# SOM_MCU.net
KiCad netlist of a schematic drawn in Altium Designer
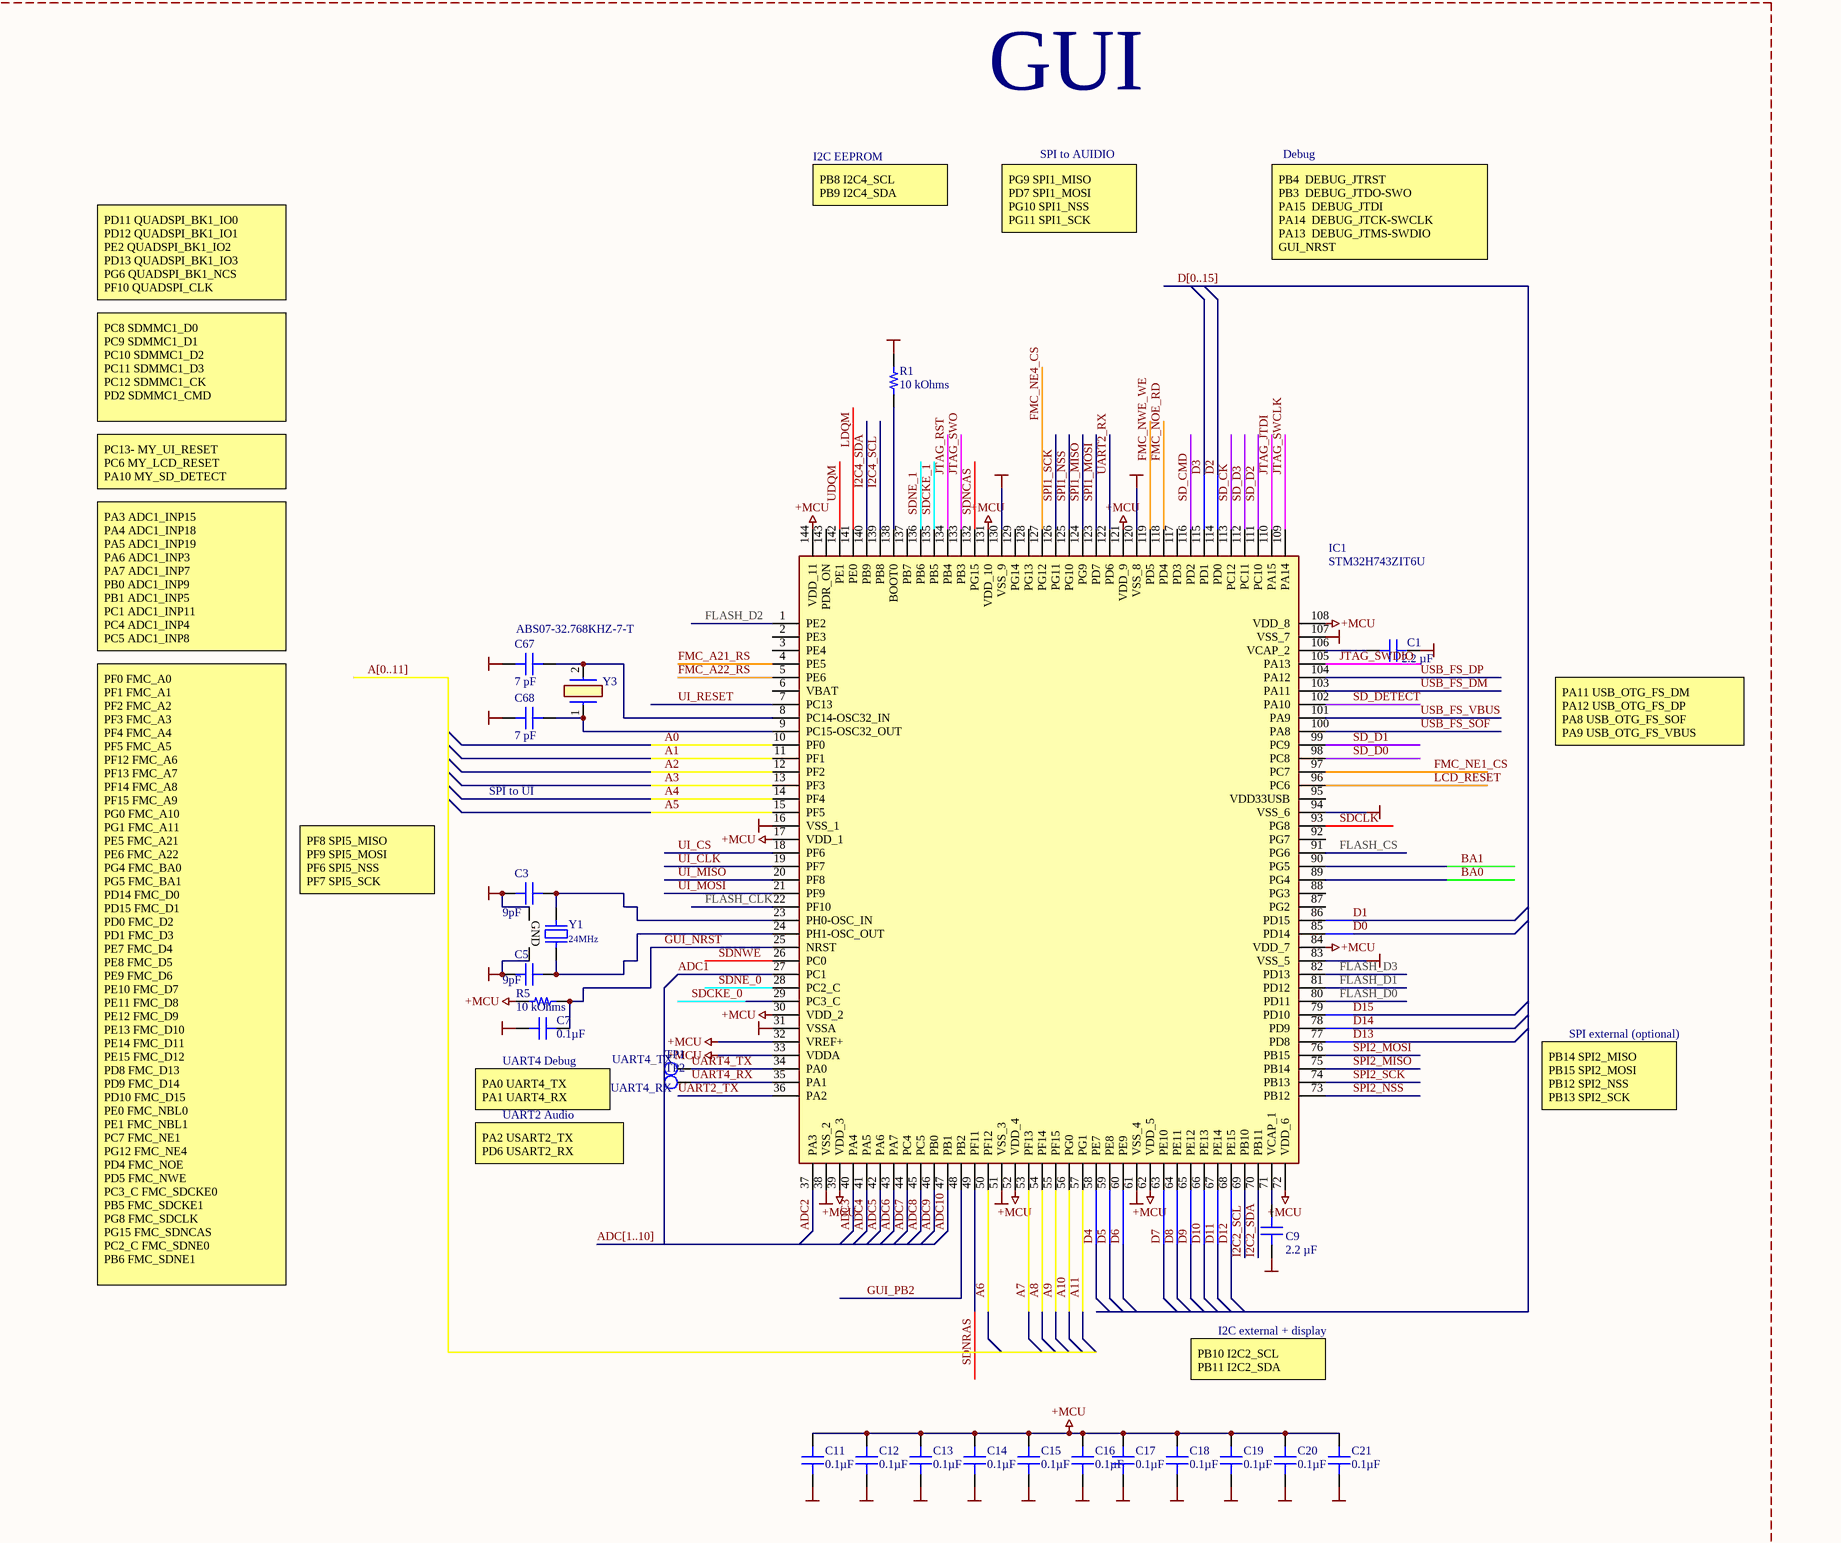
[diagram p0: SOM_MCU.SchDoc, top left]
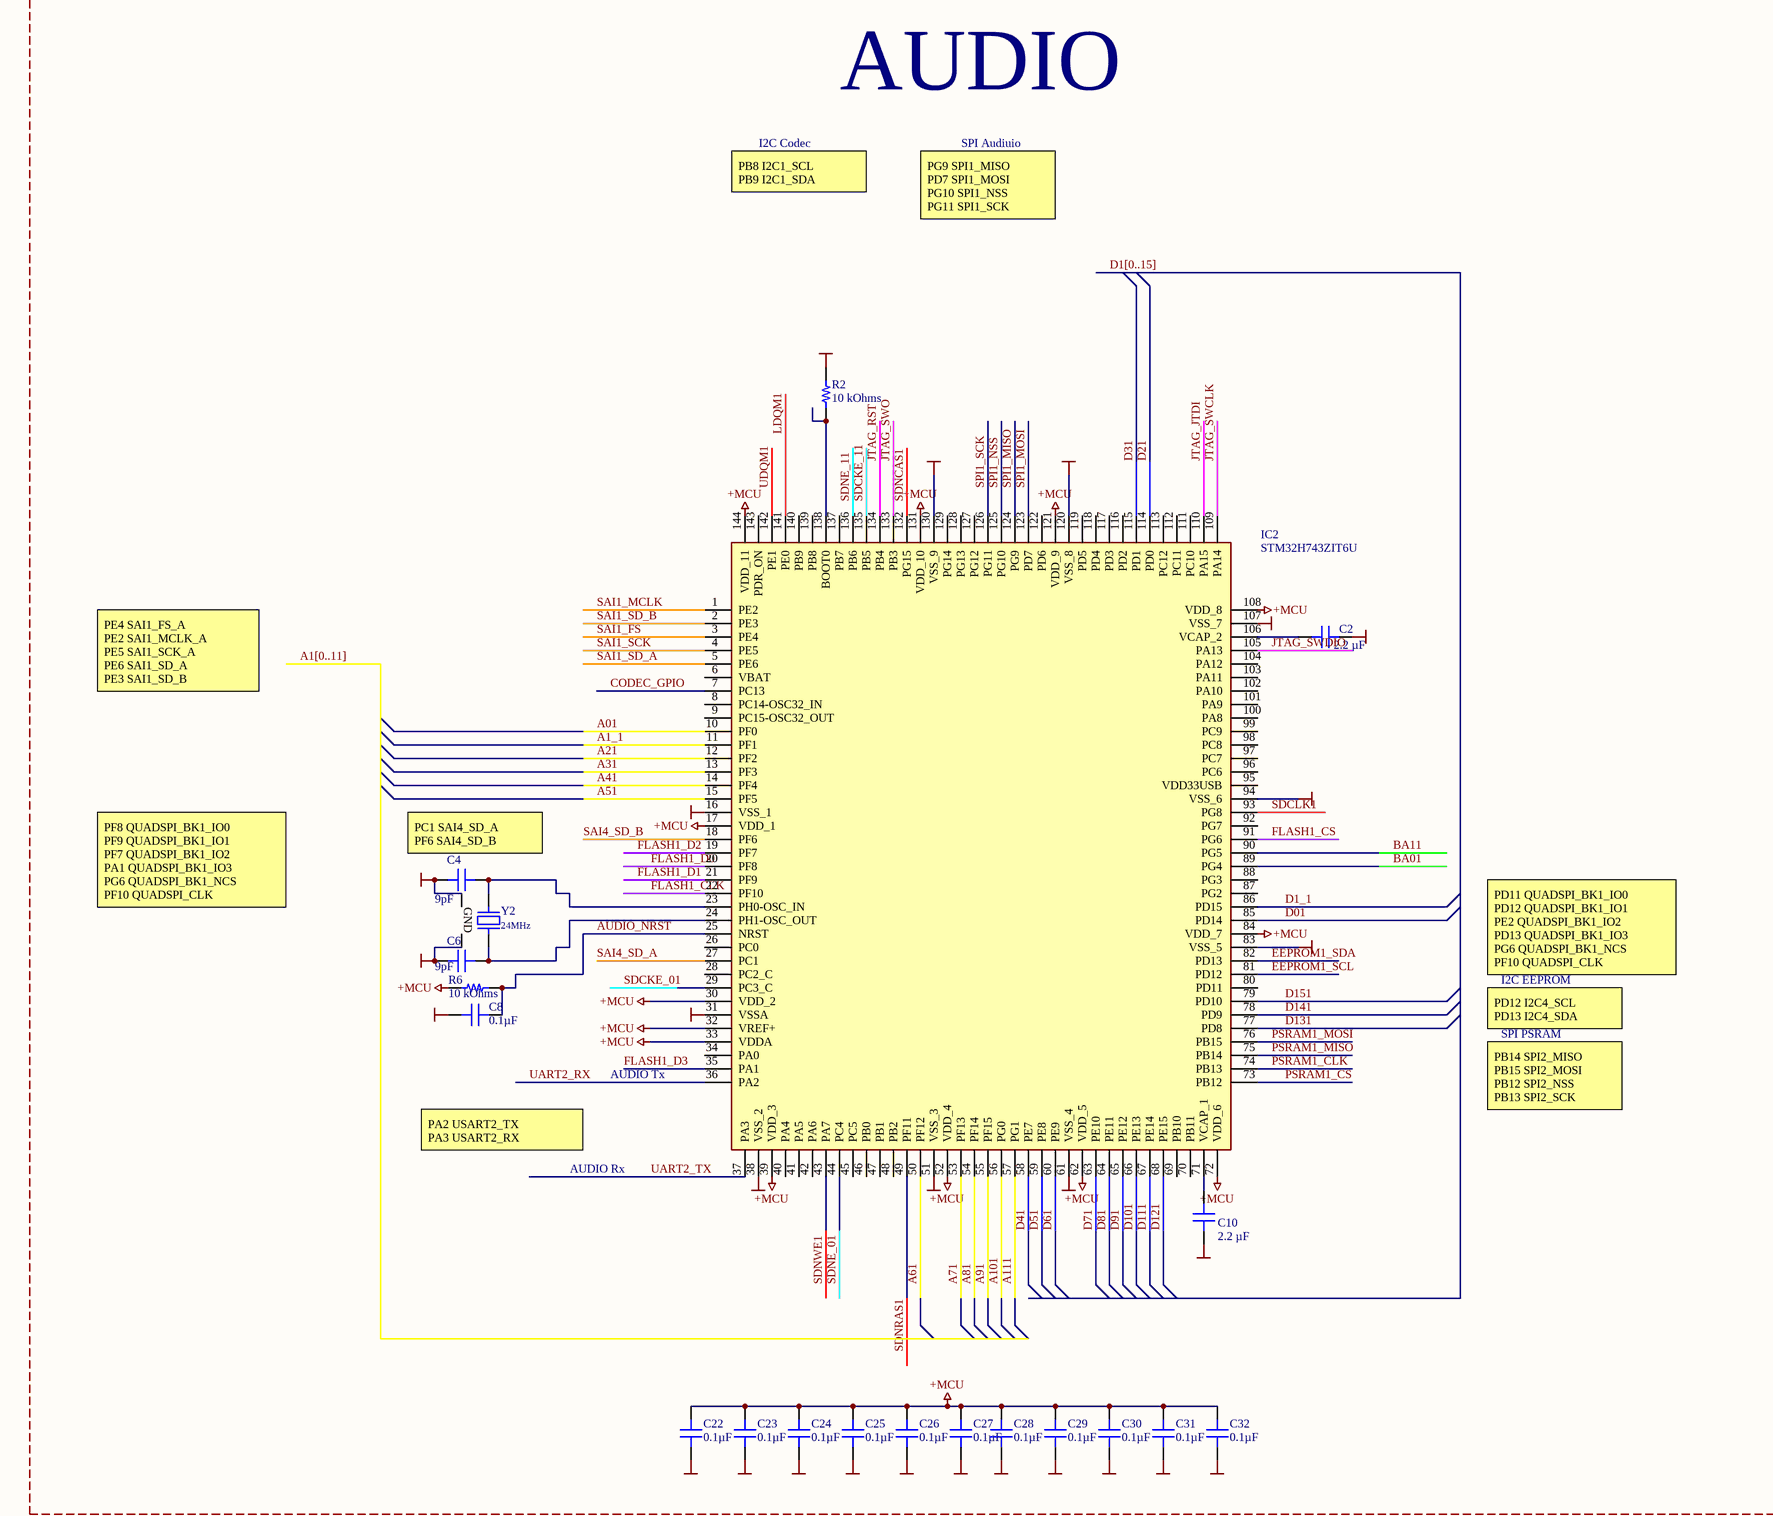
[diagram p1: SOM_MCU.SchDoc, top right]
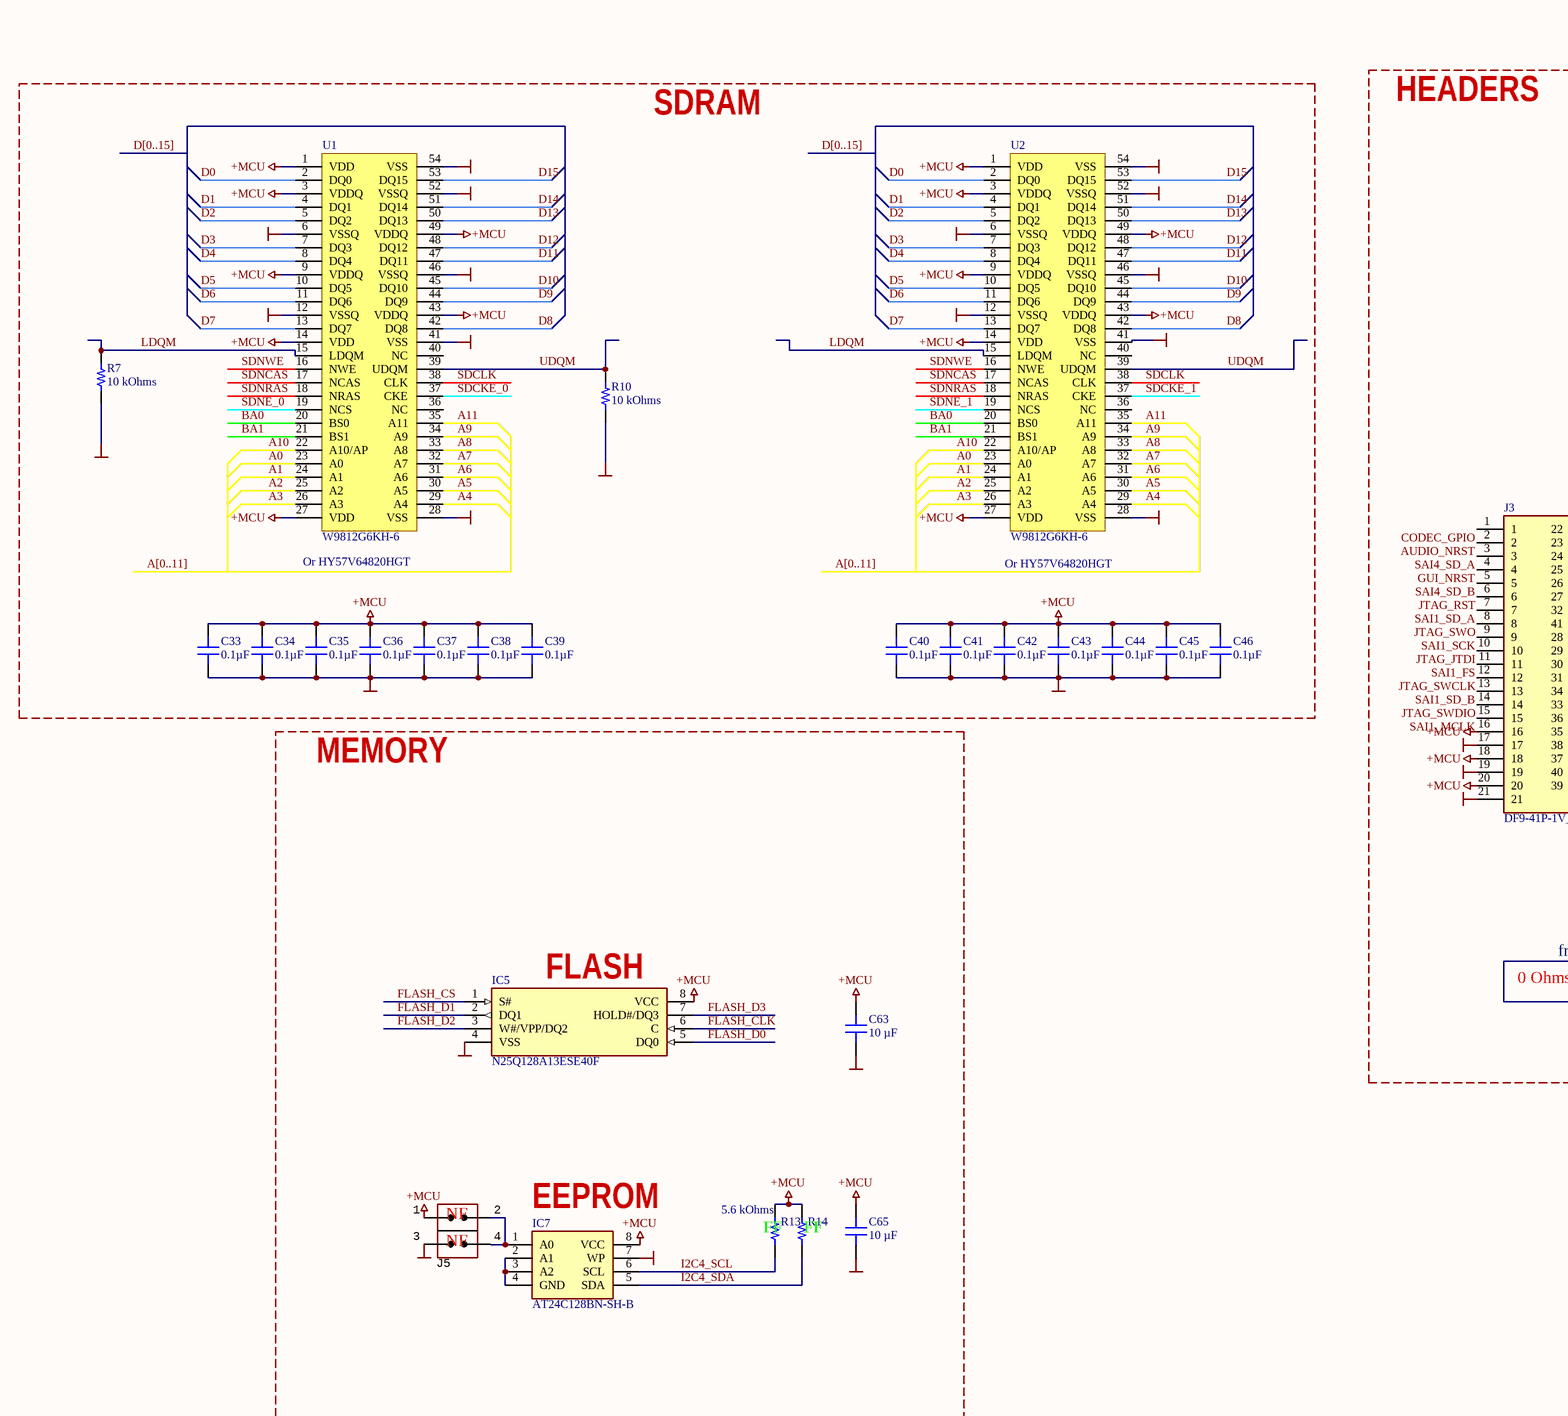
[diagram p2: SOM_MCU.SchDoc, bottom left]
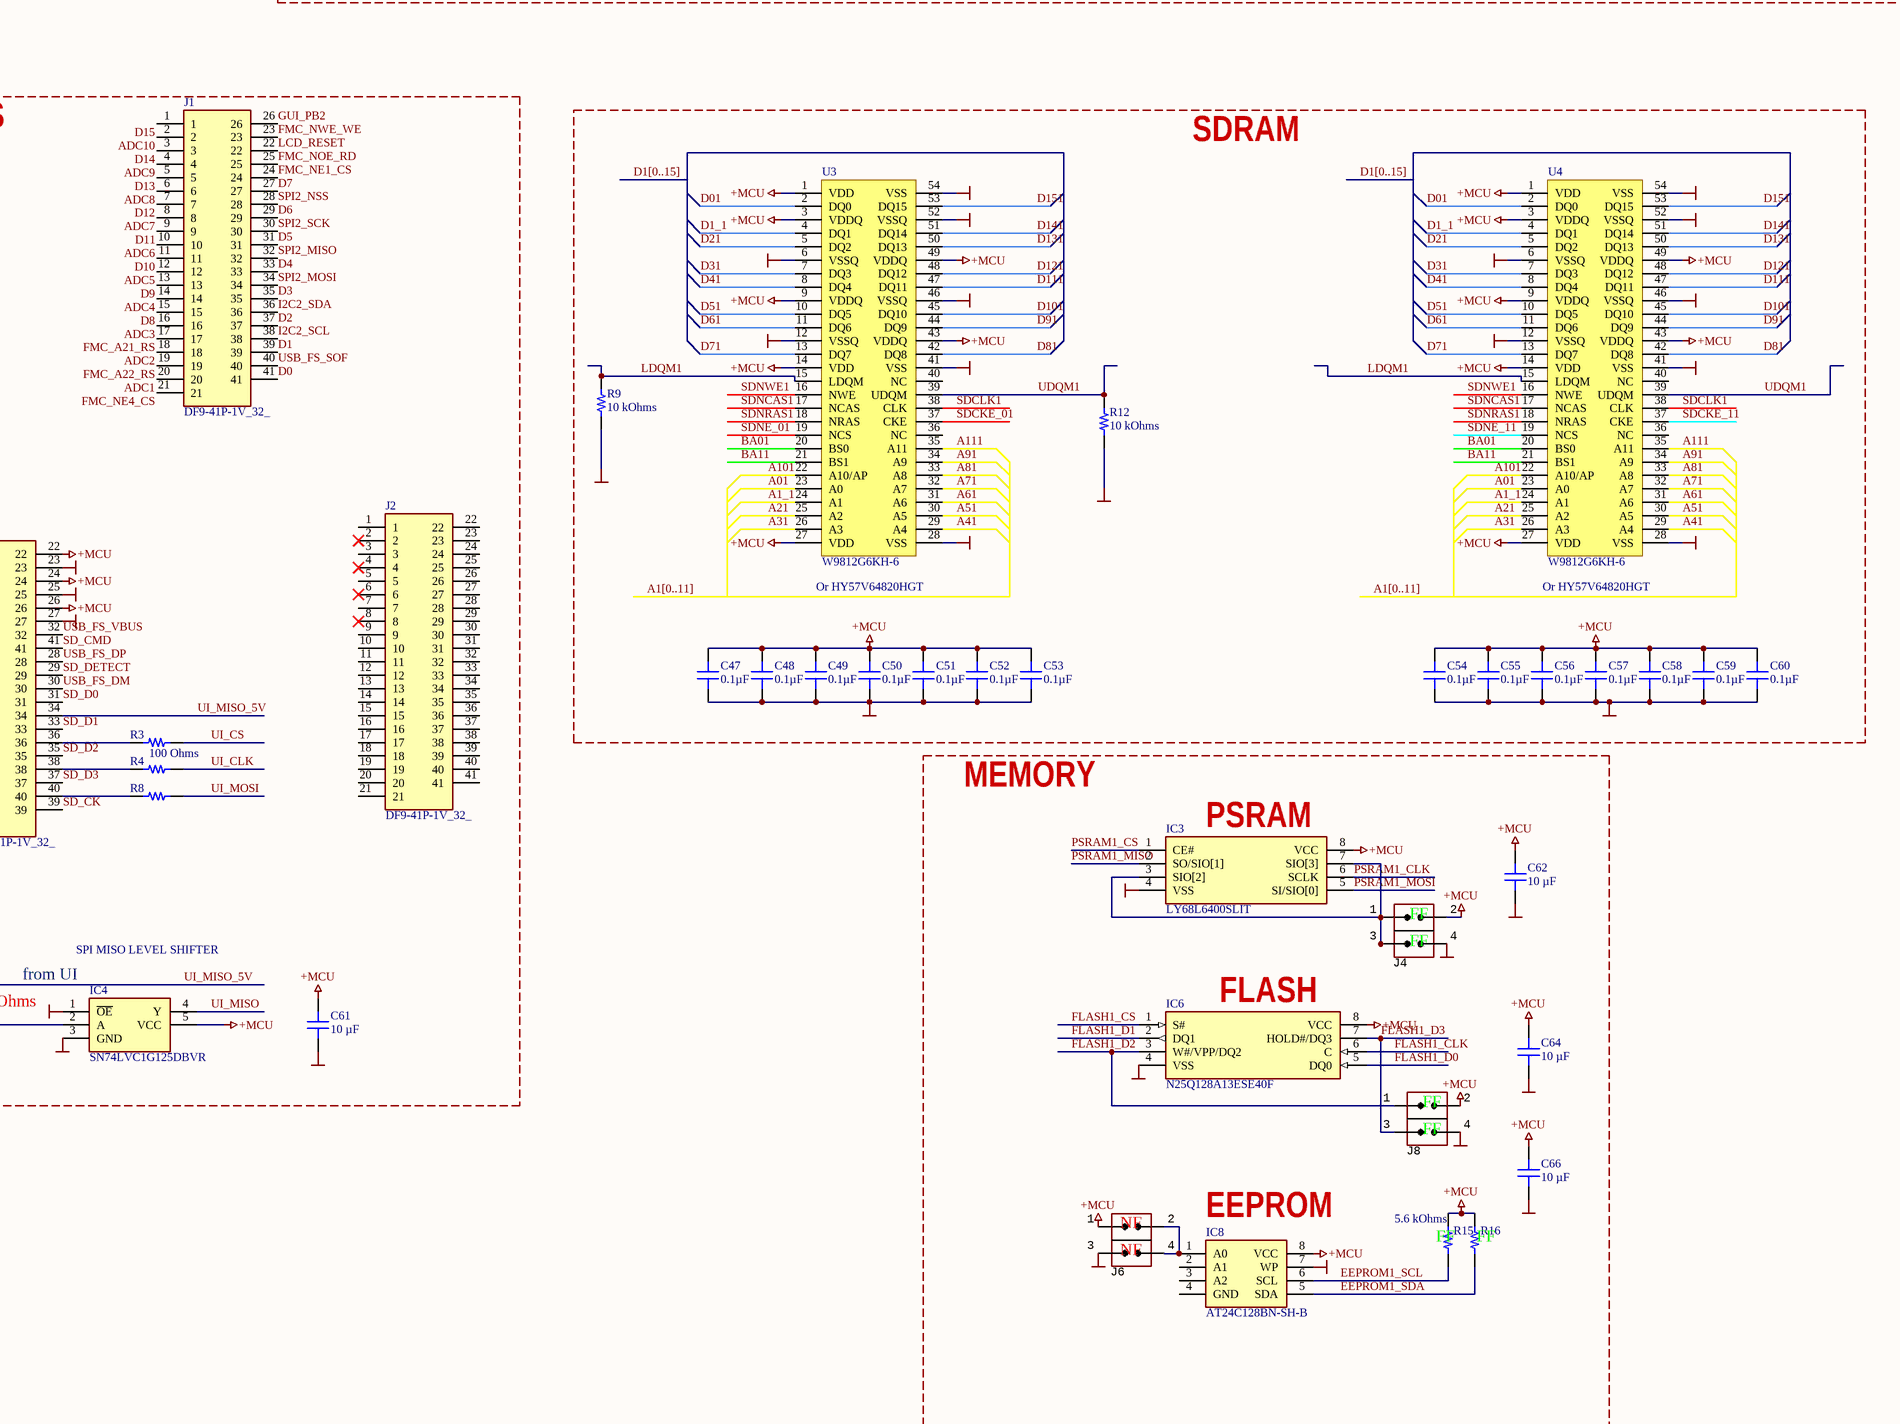
[diagram p3: SOM_MCU.SchDoc, bottom right]

(export (version "E")
  (design (tool "Eeschema 10.0.6"))
  (components
    (comp (ref "C1")
      (value "2.2 µF")
      (footprint "CAP 0805_2012")
      (description "CAP CER 2.2UF 10V X7R 0805")
      (fields (field (name "PART NUMBER") "C0805C225K8RAC7800") (field (name "MANUFACTURER") "KEMET"))
      (libsource (lib "Celestial Altium Library - altium_library") (part "Capacitor"))
    )
    (comp (ref "C2")
      (value "2.2 µF")
      (footprint "CAP 0805_2012")
      (description "CAP CER 2.2UF 10V X7R 0805")
      (fields (field (name "PART NUMBER") "C0805C225K8RAC7800") (field (name "MANUFACTURER") "KEMET"))
      (libsource (lib "Celestial Altium Library - altium_library") (part "Capacitor"))
    )
    (comp (ref "C3")
      (value "9pF")
      (footprint "CAP 0805_2012")
      (description "CAP CER 9PF 250V C0G/NP0 0805")
      (fields (field (name "PART NUMBER") "CBR08C909CAGAC") (field (name "MANUFACTURER") "KEMET"))
      (libsource (lib "Celestial Altium Library - altium_library") (part "Capacitor"))
    )
    (comp (ref "C4")
      (value "9pF")
      (footprint "CAP 0805_2012")
      (description "CAP CER 9PF 250V C0G/NP0 0805")
      (fields (field (name "PART NUMBER") "CBR08C909CAGAC") (field (name "MANUFACTURER") "KEMET"))
      (libsource (lib "Celestial Altium Library - altium_library") (part "Capacitor"))
    )
    (comp (ref "C5")
      (value "9pF")
      (footprint "CAP 0805_2012")
      (description "CAP CER 9PF 250V C0G/NP0 0805")
      (fields (field (name "PART NUMBER") "CBR08C909CAGAC") (field (name "MANUFACTURER") "KEMET"))
      (libsource (lib "Celestial Altium Library - altium_library") (part "Capacitor"))
    )
    (comp (ref "C6")
      (value "9pF")
      (footprint "CAP 0805_2012")
      (description "CAP CER 9PF 250V C0G/NP0 0805")
      (fields (field (name "PART NUMBER") "CBR08C909CAGAC") (field (name "MANUFACTURER") "KEMET"))
      (libsource (lib "Celestial Altium Library - altium_library") (part "Capacitor"))
    )
    (comp (ref "C7")
      (value "0.1µF")
      (footprint "CAP 0402_1005")
      (description "CAP CER 0.1UF 16V X7R 0402")
      (fields (field (name "PART NUMBER") "C0402C104K4RACAUTO") (field (name "MANUFACTURER") "KEMET"))
      (libsource (lib "Celestial Altium Library - altium_library") (part "Capacitor"))
    )
    (comp (ref "C8")
      (value "0.1µF")
      (footprint "CAP 0402_1005")
      (description "CAP CER 0.1UF 16V X7R 0402")
      (fields (field (name "PART NUMBER") "C0402C104K4RACAUTO") (field (name "MANUFACTURER") "KEMET"))
      (libsource (lib "Celestial Altium Library - altium_library") (part "Capacitor"))
    )
    (comp (ref "C9")
      (value "2.2 µF")
      (footprint "CAP 0805_2012")
      (description "CAP CER 2.2UF 10V X7R 0805")
      (fields (field (name "PART NUMBER") "C0805C225K8RAC7800") (field (name "MANUFACTURER") "KEMET"))
      (libsource (lib "Celestial Altium Library - altium_library") (part "Capacitor"))
    )
    (comp (ref "C10")
      (value "2.2 µF")
      (footprint "CAP 0805_2012")
      (description "CAP CER 2.2UF 10V X7R 0805")
      (fields (field (name "PART NUMBER") "C0805C225K8RAC7800") (field (name "MANUFACTURER") "KEMET"))
      (libsource (lib "Celestial Altium Library - altium_library") (part "Capacitor"))
    )
    (comp (ref "C11")
      (value "0.1µF")
      (footprint "CAP 0402_1005")
      (description "CAP CER 0.1UF 16V X7R 0402")
      (fields (field (name "PART NUMBER") "C0402C104K4RACAUTO") (field (name "MANUFACTURER") "KEMET"))
      (libsource (lib "Celestial Altium Library - altium_library") (part "Capacitor"))
    )
    (comp (ref "C12")
      (value "0.1µF")
      (footprint "CAP 0402_1005")
      (description "CAP CER 0.1UF 16V X7R 0402")
      (fields (field (name "PART NUMBER") "C0402C104K4RACAUTO") (field (name "MANUFACTURER") "KEMET"))
      (libsource (lib "Celestial Altium Library - altium_library") (part "Capacitor"))
    )
    (comp (ref "C13")
      (value "0.1µF")
      (footprint "CAP 0402_1005")
      (description "CAP CER 0.1UF 16V X7R 0402")
      (fields (field (name "PART NUMBER") "C0402C104K4RACAUTO") (field (name "MANUFACTURER") "KEMET"))
      (libsource (lib "Celestial Altium Library - altium_library") (part "Capacitor"))
    )
    (comp (ref "C14")
      (value "0.1µF")
      (footprint "CAP 0402_1005")
      (description "CAP CER 0.1UF 16V X7R 0402")
      (fields (field (name "PART NUMBER") "C0402C104K4RACAUTO") (field (name "MANUFACTURER") "KEMET"))
      (libsource (lib "Celestial Altium Library - altium_library") (part "Capacitor"))
    )
    (comp (ref "C15")
      (value "0.1µF")
      (footprint "CAP 0402_1005")
      (description "CAP CER 0.1UF 16V X7R 0402")
      (fields (field (name "PART NUMBER") "C0402C104K4RACAUTO") (field (name "MANUFACTURER") "KEMET"))
      (libsource (lib "Celestial Altium Library - altium_library") (part "Capacitor"))
    )
    (comp (ref "C16")
      (value "0.1µF")
      (footprint "CAP 0402_1005")
      (description "CAP CER 0.1UF 16V X7R 0402")
      (fields (field (name "PART NUMBER") "C0402C104K4RACAUTO") (field (name "MANUFACTURER") "KEMET"))
      (libsource (lib "Celestial Altium Library - altium_library") (part "Capacitor"))
    )
    (comp (ref "C17")
      (value "0.1µF")
      (footprint "CAP 0402_1005")
      (description "CAP CER 0.1UF 16V X7R 0402")
      (fields (field (name "PART NUMBER") "C0402C104K4RACAUTO") (field (name "MANUFACTURER") "KEMET"))
      (libsource (lib "Celestial Altium Library - altium_library") (part "Capacitor"))
    )
    (comp (ref "C18")
      (value "0.1µF")
      (footprint "CAP 0402_1005")
      (description "CAP CER 0.1UF 16V X7R 0402")
      (fields (field (name "PART NUMBER") "C0402C104K4RACAUTO") (field (name "MANUFACTURER") "KEMET"))
      (libsource (lib "Celestial Altium Library - altium_library") (part "Capacitor"))
    )
    (comp (ref "C19")
      (value "0.1µF")
      (footprint "CAP 0402_1005")
      (description "CAP CER 0.1UF 16V X7R 0402")
      (fields (field (name "PART NUMBER") "C0402C104K4RACAUTO") (field (name "MANUFACTURER") "KEMET"))
      (libsource (lib "Celestial Altium Library - altium_library") (part "Capacitor"))
    )
    (comp (ref "C20")
      (value "0.1µF")
      (footprint "CAP 0402_1005")
      (description "CAP CER 0.1UF 16V X7R 0402")
      (fields (field (name "PART NUMBER") "C0402C104K4RACAUTO") (field (name "MANUFACTURER") "KEMET"))
      (libsource (lib "Celestial Altium Library - altium_library") (part "Capacitor"))
    )
    (comp (ref "C21")
      (value "0.1µF")
      (footprint "CAP 0402_1005")
      (description "CAP CER 0.1UF 16V X7R 0402")
      (fields (field (name "PART NUMBER") "C0402C104K4RACAUTO") (field (name "MANUFACTURER") "KEMET"))
      (libsource (lib "Celestial Altium Library - altium_library") (part "Capacitor"))
    )
    (comp (ref "C22")
      (value "0.1µF")
      (footprint "CAP 0402_1005")
      (description "CAP CER 0.1UF 16V X7R 0402")
      (fields (field (name "PART NUMBER") "C0402C104K4RACAUTO") (field (name "MANUFACTURER") "KEMET"))
      (libsource (lib "Celestial Altium Library - altium_library") (part "Capacitor"))
    )
    (comp (ref "C23")
      (value "0.1µF")
      (footprint "CAP 0402_1005")
      (description "CAP CER 0.1UF 16V X7R 0402")
      (fields (field (name "PART NUMBER") "C0402C104K4RACAUTO") (field (name "MANUFACTURER") "KEMET"))
      (libsource (lib "Celestial Altium Library - altium_library") (part "Capacitor"))
    )
    (comp (ref "C24")
      (value "0.1µF")
      (footprint "CAP 0402_1005")
      (description "CAP CER 0.1UF 16V X7R 0402")
      (fields (field (name "PART NUMBER") "C0402C104K4RACAUTO") (field (name "MANUFACTURER") "KEMET"))
      (libsource (lib "Celestial Altium Library - altium_library") (part "Capacitor"))
    )
    (comp (ref "C25")
      (value "0.1µF")
      (footprint "CAP 0402_1005")
      (description "CAP CER 0.1UF 16V X7R 0402")
      (fields (field (name "PART NUMBER") "C0402C104K4RACAUTO") (field (name "MANUFACTURER") "KEMET"))
      (libsource (lib "Celestial Altium Library - altium_library") (part "Capacitor"))
    )
    (comp (ref "C26")
      (value "0.1µF")
      (footprint "CAP 0402_1005")
      (description "CAP CER 0.1UF 16V X7R 0402")
      (fields (field (name "PART NUMBER") "C0402C104K4RACAUTO") (field (name "MANUFACTURER") "KEMET"))
      (libsource (lib "Celestial Altium Library - altium_library") (part "Capacitor"))
    )
    (comp (ref "C27")
      (value "0.1µF")
      (footprint "CAP 0402_1005")
      (description "CAP CER 0.1UF 16V X7R 0402")
      (fields (field (name "PART NUMBER") "C0402C104K4RACAUTO") (field (name "MANUFACTURER") "KEMET"))
      (libsource (lib "Celestial Altium Library - altium_library") (part "Capacitor"))
    )
    (comp (ref "C28")
      (value "0.1µF")
      (footprint "CAP 0402_1005")
      (description "CAP CER 0.1UF 16V X7R 0402")
      (fields (field (name "PART NUMBER") "C0402C104K4RACAUTO") (field (name "MANUFACTURER") "KEMET"))
      (libsource (lib "Celestial Altium Library - altium_library") (part "Capacitor"))
    )
    (comp (ref "C29")
      (value "0.1µF")
      (footprint "CAP 0402_1005")
      (description "CAP CER 0.1UF 16V X7R 0402")
      (fields (field (name "PART NUMBER") "C0402C104K4RACAUTO") (field (name "MANUFACTURER") "KEMET"))
      (libsource (lib "Celestial Altium Library - altium_library") (part "Capacitor"))
    )
    (comp (ref "C30")
      (value "0.1µF")
      (footprint "CAP 0402_1005")
      (description "CAP CER 0.1UF 16V X7R 0402")
      (fields (field (name "PART NUMBER") "C0402C104K4RACAUTO") (field (name "MANUFACTURER") "KEMET"))
      (libsource (lib "Celestial Altium Library - altium_library") (part "Capacitor"))
    )
    (comp (ref "C31")
      (value "0.1µF")
      (footprint "CAP 0402_1005")
      (description "CAP CER 0.1UF 16V X7R 0402")
      (fields (field (name "PART NUMBER") "C0402C104K4RACAUTO") (field (name "MANUFACTURER") "KEMET"))
      (libsource (lib "Celestial Altium Library - altium_library") (part "Capacitor"))
    )
    (comp (ref "C32")
      (value "0.1µF")
      (footprint "CAP 0402_1005")
      (description "CAP CER 0.1UF 16V X7R 0402")
      (fields (field (name "PART NUMBER") "C0402C104K4RACAUTO") (field (name "MANUFACTURER") "KEMET"))
      (libsource (lib "Celestial Altium Library - altium_library") (part "Capacitor"))
    )
    (comp (ref "C33")
      (value "0.1µF")
      (footprint "CAP 0402_1005")
      (description "CAP CER 0.1UF 16V X7R 0402")
      (fields (field (name "PART NUMBER") "C0402C104K4RACAUTO") (field (name "MANUFACTURER") "KEMET"))
      (libsource (lib "Celestial Altium Library - altium_library") (part "Capacitor"))
    )
    (comp (ref "C34")
      (value "0.1µF")
      (footprint "CAP 0402_1005")
      (description "CAP CER 0.1UF 16V X7R 0402")
      (fields (field (name "PART NUMBER") "C0402C104K4RACAUTO") (field (name "MANUFACTURER") "KEMET"))
      (libsource (lib "Celestial Altium Library - altium_library") (part "Capacitor"))
    )
    (comp (ref "C35")
      (value "0.1µF")
      (footprint "CAP 0402_1005")
      (description "CAP CER 0.1UF 16V X7R 0402")
      (fields (field (name "PART NUMBER") "C0402C104K4RACAUTO") (field (name "MANUFACTURER") "KEMET"))
      (libsource (lib "Celestial Altium Library - altium_library") (part "Capacitor"))
    )
    (comp (ref "C36")
      (value "0.1µF")
      (footprint "CAP 0402_1005")
      (description "CAP CER 0.1UF 16V X7R 0402")
      (fields (field (name "PART NUMBER") "C0402C104K4RACAUTO") (field (name "MANUFACTURER") "KEMET"))
      (libsource (lib "Celestial Altium Library - altium_library") (part "Capacitor"))
    )
    (comp (ref "C37")
      (value "0.1µF")
      (footprint "CAP 0402_1005")
      (description "CAP CER 0.1UF 16V X7R 0402")
      (fields (field (name "PART NUMBER") "C0402C104K4RACAUTO") (field (name "MANUFACTURER") "KEMET"))
      (libsource (lib "Celestial Altium Library - altium_library") (part "Capacitor"))
    )
    (comp (ref "C38")
      (value "0.1µF")
      (footprint "CAP 0402_1005")
      (description "CAP CER 0.1UF 16V X7R 0402")
      (fields (field (name "PART NUMBER") "C0402C104K4RACAUTO") (field (name "MANUFACTURER") "KEMET"))
      (libsource (lib "Celestial Altium Library - altium_library") (part "Capacitor"))
    )
    (comp (ref "C39")
      (value "0.1µF")
      (footprint "CAP 0402_1005")
      (description "CAP CER 0.1UF 16V X7R 0402")
      (fields (field (name "PART NUMBER") "C0402C104K4RACAUTO") (field (name "MANUFACTURER") "KEMET"))
      (libsource (lib "Celestial Altium Library - altium_library") (part "Capacitor"))
    )
    (comp (ref "C40")
      (value "0.1µF")
      (footprint "CAP 0402_1005")
      (description "CAP CER 0.1UF 16V X7R 0402")
      (fields (field (name "PART NUMBER") "C0402C104K4RACAUTO") (field (name "MANUFACTURER") "KEMET"))
      (libsource (lib "Celestial Altium Library - altium_library") (part "Capacitor"))
    )
    (comp (ref "C41")
      (value "0.1µF")
      (footprint "CAP 0402_1005")
      (description "CAP CER 0.1UF 16V X7R 0402")
      (fields (field (name "PART NUMBER") "C0402C104K4RACAUTO") (field (name "MANUFACTURER") "KEMET"))
      (libsource (lib "Celestial Altium Library - altium_library") (part "Capacitor"))
    )
    (comp (ref "C42")
      (value "0.1µF")
      (footprint "CAP 0402_1005")
      (description "CAP CER 0.1UF 16V X7R 0402")
      (fields (field (name "PART NUMBER") "C0402C104K4RACAUTO") (field (name "MANUFACTURER") "KEMET"))
      (libsource (lib "Celestial Altium Library - altium_library") (part "Capacitor"))
    )
    (comp (ref "C43")
      (value "0.1µF")
      (footprint "CAP 0402_1005")
      (description "CAP CER 0.1UF 16V X7R 0402")
      (fields (field (name "PART NUMBER") "C0402C104K4RACAUTO") (field (name "MANUFACTURER") "KEMET"))
      (libsource (lib "Celestial Altium Library - altium_library") (part "Capacitor"))
    )
    (comp (ref "C44")
      (value "0.1µF")
      (footprint "CAP 0402_1005")
      (description "CAP CER 0.1UF 16V X7R 0402")
      (fields (field (name "PART NUMBER") "C0402C104K4RACAUTO") (field (name "MANUFACTURER") "KEMET"))
      (libsource (lib "Celestial Altium Library - altium_library") (part "Capacitor"))
    )
    (comp (ref "C45")
      (value "0.1µF")
      (footprint "CAP 0402_1005")
      (description "CAP CER 0.1UF 16V X7R 0402")
      (fields (field (name "PART NUMBER") "C0402C104K4RACAUTO") (field (name "MANUFACTURER") "KEMET"))
      (libsource (lib "Celestial Altium Library - altium_library") (part "Capacitor"))
    )
    (comp (ref "C46")
      (value "0.1µF")
      (footprint "CAP 0402_1005")
      (description "CAP CER 0.1UF 16V X7R 0402")
      (fields (field (name "PART NUMBER") "C0402C104K4RACAUTO") (field (name "MANUFACTURER") "KEMET"))
      (libsource (lib "Celestial Altium Library - altium_library") (part "Capacitor"))
    )
    (comp (ref "C47")
      (value "0.1µF")
      (footprint "CAP 0402_1005")
      (description "CAP CER 0.1UF 16V X7R 0402")
      (fields (field (name "PART NUMBER") "C0402C104K4RACAUTO") (field (name "MANUFACTURER") "KEMET"))
      (libsource (lib "Celestial Altium Library - altium_library") (part "Capacitor"))
    )
    (comp (ref "C48")
      (value "0.1µF")
      (footprint "CAP 0402_1005")
      (description "CAP CER 0.1UF 16V X7R 0402")
      (fields (field (name "PART NUMBER") "C0402C104K4RACAUTO") (field (name "MANUFACTURER") "KEMET"))
      (libsource (lib "Celestial Altium Library - altium_library") (part "Capacitor"))
    )
    (comp (ref "C49")
      (value "0.1µF")
      (footprint "CAP 0402_1005")
      (description "CAP CER 0.1UF 16V X7R 0402")
      (fields (field (name "PART NUMBER") "C0402C104K4RACAUTO") (field (name "MANUFACTURER") "KEMET"))
      (libsource (lib "Celestial Altium Library - altium_library") (part "Capacitor"))
    )
    (comp (ref "C50")
      (value "0.1µF")
      (footprint "CAP 0402_1005")
      (description "CAP CER 0.1UF 16V X7R 0402")
      (fields (field (name "PART NUMBER") "C0402C104K4RACAUTO") (field (name "MANUFACTURER") "KEMET"))
      (libsource (lib "Celestial Altium Library - altium_library") (part "Capacitor"))
    )
    (comp (ref "C51")
      (value "0.1µF")
      (footprint "CAP 0402_1005")
      (description "CAP CER 0.1UF 16V X7R 0402")
      (fields (field (name "PART NUMBER") "C0402C104K4RACAUTO") (field (name "MANUFACTURER") "KEMET"))
      (libsource (lib "Celestial Altium Library - altium_library") (part "Capacitor"))
    )
    (comp (ref "C52")
      (value "0.1µF")
      (footprint "CAP 0402_1005")
      (description "CAP CER 0.1UF 16V X7R 0402")
      (fields (field (name "PART NUMBER") "C0402C104K4RACAUTO") (field (name "MANUFACTURER") "KEMET"))
      (libsource (lib "Celestial Altium Library - altium_library") (part "Capacitor"))
    )
    (comp (ref "C53")
      (value "0.1µF")
      (footprint "CAP 0402_1005")
      (description "CAP CER 0.1UF 16V X7R 0402")
      (fields (field (name "PART NUMBER") "C0402C104K4RACAUTO") (field (name "MANUFACTURER") "KEMET"))
      (libsource (lib "Celestial Altium Library - altium_library") (part "Capacitor"))
    )
    (comp (ref "C54")
      (value "0.1µF")
      (footprint "CAP 0402_1005")
      (description "CAP CER 0.1UF 16V X7R 0402")
      (fields (field (name "PART NUMBER") "C0402C104K4RACAUTO") (field (name "MANUFACTURER") "KEMET"))
      (libsource (lib "Celestial Altium Library - altium_library") (part "Capacitor"))
    )
    (comp (ref "C55")
      (value "0.1µF")
      (footprint "CAP 0402_1005")
      (description "CAP CER 0.1UF 16V X7R 0402")
      (fields (field (name "PART NUMBER") "C0402C104K4RACAUTO") (field (name "MANUFACTURER") "KEMET"))
      (libsource (lib "Celestial Altium Library - altium_library") (part "Capacitor"))
    )
    (comp (ref "C56")
      (value "0.1µF")
      (footprint "CAP 0402_1005")
      (description "CAP CER 0.1UF 16V X7R 0402")
      (fields (field (name "PART NUMBER") "C0402C104K4RACAUTO") (field (name "MANUFACTURER") "KEMET"))
      (libsource (lib "Celestial Altium Library - altium_library") (part "Capacitor"))
    )
    (comp (ref "C57")
      (value "0.1µF")
      (footprint "CAP 0402_1005")
      (description "CAP CER 0.1UF 16V X7R 0402")
      (fields (field (name "PART NUMBER") "C0402C104K4RACAUTO") (field (name "MANUFACTURER") "KEMET"))
      (libsource (lib "Celestial Altium Library - altium_library") (part "Capacitor"))
    )
    (comp (ref "C58")
      (value "0.1µF")
      (footprint "CAP 0402_1005")
      (description "CAP CER 0.1UF 16V X7R 0402")
      (fields (field (name "PART NUMBER") "C0402C104K4RACAUTO") (field (name "MANUFACTURER") "KEMET"))
      (libsource (lib "Celestial Altium Library - altium_library") (part "Capacitor"))
    )
    (comp (ref "C59")
      (value "0.1µF")
      (footprint "CAP 0402_1005")
      (description "CAP CER 0.1UF 16V X7R 0402")
      (fields (field (name "PART NUMBER") "C0402C104K4RACAUTO") (field (name "MANUFACTURER") "KEMET"))
      (libsource (lib "Celestial Altium Library - altium_library") (part "Capacitor"))
    )
    (comp (ref "C60")
      (value "0.1µF")
      (footprint "CAP 0402_1005")
      (description "CAP CER 0.1UF 16V X7R 0402")
      (fields (field (name "PART NUMBER") "C0402C104K4RACAUTO") (field (name "MANUFACTURER") "KEMET"))
      (libsource (lib "Celestial Altium Library - altium_library") (part "Capacitor"))
    )
    (comp (ref "C61")
      (value "10 µF")
      (footprint "CAP 0805_2012")
      (description "CAP CER 10UF 10V X5R 0805")
      (fields (field (name "PART NUMBER") "C0805C106K8PAC7800") (field (name "MANUFACTURER") "KEMET"))
      (libsource (lib "Celestial Altium Library - altium_library") (part "Capacitor"))
    )
    (comp (ref "C62")
      (value "10 µF")
      (footprint "CAP 0805_2012")
      (description "CAP CER 10UF 10V X5R 0805")
      (fields (field (name "PART NUMBER") "C0805C106K8PAC7800") (field (name "MANUFACTURER") "KEMET"))
      (libsource (lib "Celestial Altium Library - altium_library") (part "Capacitor"))
    )
    (comp (ref "C63")
      (value "10 µF")
      (footprint "CAP 0805_2012")
      (description "CAP CER 10UF 10V X5R 0805")
      (fields (field (name "PART NUMBER") "C0805C106K8PAC7800") (field (name "MANUFACTURER") "KEMET"))
      (libsource (lib "Celestial Altium Library - altium_library") (part "Capacitor"))
    )
    (comp (ref "C64")
      (value "10 µF")
      (footprint "CAP 0805_2012")
      (description "CAP CER 10UF 10V X5R 0805")
      (fields (field (name "PART NUMBER") "C0805C106K8PAC7800") (field (name "MANUFACTURER") "KEMET"))
      (libsource (lib "Celestial Altium Library - altium_library") (part "Capacitor"))
    )
    (comp (ref "C65")
      (value "10 µF")
      (footprint "CAP 0805_2012")
      (description "CAP CER 10UF 10V X5R 0805")
      (fields (field (name "PART NUMBER") "C0805C106K8PAC7800") (field (name "MANUFACTURER") "KEMET"))
      (libsource (lib "Celestial Altium Library - altium_library") (part "Capacitor"))
    )
    (comp (ref "C66")
      (value "10 µF")
      (footprint "CAP 0805_2012")
      (description "CAP CER 10UF 10V X5R 0805")
      (fields (field (name "PART NUMBER") "C0805C106K8PAC7800") (field (name "MANUFACTURER") "KEMET"))
      (libsource (lib "Celestial Altium Library - altium_library") (part "Capacitor"))
    )
    (comp (ref "C67")
      (value "7 pF")
      (footprint "CAP 0805_2012")
      (description "CAP CER 7PF 50V C0G/NPO 0805")
      (fields (field (name "PART NUMBER") "CC0805DRNPO9BN7R0") (field (name "MANUFACTURER") "Yageo"))
      (libsource (lib "Celestial Altium Library - altium_library") (part "Capacitor"))
    )
    (comp (ref "C68")
      (value "7 pF")
      (footprint "CAP 0805_2012")
      (description "CAP CER 7PF 50V C0G/NPO 0805")
      (fields (field (name "PART NUMBER") "CC0805DRNPO9BN7R0") (field (name "MANUFACTURER") "Yageo"))
      (libsource (lib "Celestial Altium Library - altium_library") (part "Capacitor"))
    )
    (comp (ref "IC1")
      (value "STM32H743ZIT6U")
      (footprint "ProtoStack_H750VBT:QFP50P2200X2200X160-144N")
      (description "Integrated Circuit")
      (libsource (lib "ProtoStack_H750VBT") (part "STM32H743ZIT6U"))
    )
    (comp (ref "IC2")
      (value "STM32H743ZIT6U")
      (footprint "QFP50P2200X2200X160-144N")
      (description "Integrated Circuit")
      (libsource (lib "ProtoStack_H750VBT") (part "STM32H743ZIT6U"))
    )
    (comp (ref "IC3")
      (value "LY68L6400SLIT")
      (footprint "ProtoStack_H750VBT:SOIC127P600X175-8N")
      (description "Integrated Circuit")
      (libsource (lib "ProtoStack_H750VBT") (part "LY68L6400SLIT"))
    )
    (comp (ref "IC4")
      (value "SN74LVC1G125DBVR")
      (footprint "ProtoStack_H750VBT:SOT95P280X145-5N")
      (description "Integrated Circuit")
      (fields (field (name "MOUSER PART NUMBER") "595-SN74LVC1G125DBVR"))
      (libsource (lib "ProtoStack_H750VBT") (part "SN74LVC1G125DBVR"))
    )
    (comp (ref "IC5")
      (value "N25Q128A13ESE40F")
      (footprint "SOIC127P790X216-8N")
      (description "Integrated Circuit")
      (fields (field (name "MOUSER PART NUMBER") "340-182267"))
      (libsource (lib "ProtoStack_H750VBT") (part "N25Q128A13ESE40F"))
    )
    (comp (ref "IC6")
      (value "N25Q128A13ESE40F")
      (footprint "SOIC127P790X216-8N")
      (description "Integrated Circuit")
      (fields (field (name "MOUSER PART NUMBER") "340-182267"))
      (libsource (lib "ProtoStack_H750VBT") (part "N25Q128A13ESE40F"))
    )
    (comp (ref "IC7")
      (value "AT24C128BN-SH-B")
      (footprint "ProtoStack_H750VBT:SOIC127P600X175-8N")
      (description "Integrated Circuit")
      (fields (field (name "MOUSER PART NUMBER") "556-A24C128BNSH-B"))
      (libsource (lib "ProtoStack_H750VBT") (part "AT24C128BN-SH-B"))
    )
    (comp (ref "IC8")
      (value "AT24C128BN-SH-B")
      (footprint "ProtoStack_H750VBT:SOIC127P600X175-8N")
      (description "Integrated Circuit")
      (fields (field (name "MOUSER PART NUMBER") "556-A24C128BNSH-B"))
      (libsource (lib "ProtoStack_H750VBT") (part "AT24C128BN-SH-B"))
    )
    (comp (ref "J1")
      (value "DF9-41P-1V_32_")
      (footprint "ProtoStack_H750VBT:HIROSE_DF9-41P-1V(32)")
      (description "Connector")
      (fields
        (field (name "MANUFACTURER_PART_NUMBER") "DF9-41P-1V(32)")
        (field (name "MOUSER PART NUMBER") "798-DF9-41P-1V32")
      )
      (libsource (lib "ProtoStack_H750VBT") (part "DF9-41P-1V_32_"))
    )
    (comp (ref "J2")
      (value "DF9-41P-1V_32_")
      (footprint "ProtoStack_H750VBT:HIROSE_DF9-41P-1V(32)")
      (description "Connector")
      (fields
        (field (name "MANUFACTURER_PART_NUMBER") "DF9-41P-1V(32)")
        (field (name "MOUSER PART NUMBER") "798-DF9-41P-1V32")
      )
      (libsource (lib "") (part "DF9-41P-1V_32__1"))
    )
    (comp (ref "J3")
      (value "DF9-41P-1V_32_")
      (footprint "ProtoStack_H750VBT:HIROSE_DF9-41P-1V(32)")
      (description "Connector")
      (fields
        (field (name "MANUFACTURER_PART_NUMBER") "DF9-41P-1V(32)")
        (field (name "MOUSER PART NUMBER") "798-DF9-41P-1V32")
      )
      (libsource (lib "") (part "DF9-41P-1V_32__2"))
    )
    (comp (ref "J4")
      (value "~")
      (footprint "CON: JUMPER x2")
      (libsource (lib "connector") (part "Jumper_double"))
    )
    (comp (ref "J5")
      (value "~")
      (footprint "CON: JUMPER x2")
      (libsource (lib "connector") (part "Jumper_double"))
    )
    (comp (ref "J6")
      (value "~")
      (footprint "CON: JUMPER x2")
      (libsource (lib "connector") (part "Jumper_double"))
    )
    (comp (ref "J8")
      (value "~")
      (footprint "CON: JUMPER x2")
      (libsource (lib "connector") (part "Jumper_double"))
    )
    (comp (ref "R1")
      (value "10 kOhms")
      (footprint "RES 0603_1608")
      (description "RES SMD 10K OHM 1% 1/10W 0603")
      (fields (field (name "PART NUMBER") "RT0603FRE0710KL") (field (name "MANUFACTURER") "Yageo"))
      (libsource (lib "Celestial Altium Library - altium_library") (part "Resistor"))
    )
    (comp (ref "R2")
      (value "10 kOhms")
      (footprint "RES 0603_1608")
      (description "RES SMD 10K OHM 1% 1/10W 0603")
      (fields (field (name "PART NUMBER") "RT0603FRE0710KL") (field (name "MANUFACTURER") "Yageo"))
      (libsource (lib "Celestial Altium Library - altium_library") (part "Resistor"))
    )
    (comp (ref "R3")
      (value "100 Ohms")
      (footprint "RES 0402_1005")
      (description "RES SMD 100 OHM 1% 1/16W 0402")
      (fields (field (name "PART NUMBER") "RT0402FRE07100RL") (field (name "MANUFACTURER") "Yageo"))
      (libsource (lib "Celestial Altium Library - altium_library") (part "Resistor"))
    )
    (comp (ref "R4")
      (value "100 Ohms")
      (footprint "RES 0402_1005")
      (description "RES SMD 100 OHM 1% 1/16W 0402")
      (fields (field (name "PART NUMBER") "RT0402FRE07100RL") (field (name "MANUFACTURER") "Yageo"))
      (libsource (lib "Celestial Altium Library - altium_library") (part "Resistor"))
    )
    (comp (ref "R5")
      (value "10 kOhms")
      (footprint "RES 0603_1608")
      (description "RES SMD 10K OHM 1% 1/10W 0603")
      (fields (field (name "PART NUMBER") "RT0603FRE0710KL") (field (name "MANUFACTURER") "Yageo"))
      (libsource (lib "Celestial Altium Library - altium_library") (part "Resistor"))
    )
    (comp (ref "R6")
      (value "10 kOhms")
      (footprint "RES 0603_1608")
      (description "RES SMD 10K OHM 1% 1/10W 0603")
      (fields (field (name "PART NUMBER") "RT0603FRE0710KL") (field (name "MANUFACTURER") "Yageo"))
      (libsource (lib "Celestial Altium Library - altium_library") (part "Resistor"))
    )
    (comp (ref "R7")
      (value "10 kOhms")
      (footprint "RES 0603_1608")
      (description "RES SMD 10K OHM 1% 1/10W 0603")
      (fields (field (name "PART NUMBER") "RT0603FRE0710KL") (field (name "MANUFACTURER") "Yageo"))
      (libsource (lib "Celestial Altium Library - altium_library") (part "Resistor"))
    )
    (comp (ref "R8")
      (value "100 Ohms")
      (footprint "RES 0402_1005")
      (description "RES SMD 100 OHM 1% 1/16W 0402")
      (fields (field (name "PART NUMBER") "RT0402FRE07100RL") (field (name "MANUFACTURER") "Yageo"))
      (libsource (lib "Celestial Altium Library - altium_library") (part "Resistor"))
    )
    (comp (ref "R9")
      (value "10 kOhms")
      (footprint "RES 0603_1608")
      (description "RES SMD 10K OHM 1% 1/10W 0603")
      (fields (field (name "PART NUMBER") "RT0603FRE0710KL") (field (name "MANUFACTURER") "Yageo"))
      (libsource (lib "Celestial Altium Library - altium_library") (part "Resistor"))
    )
    (comp (ref "R10")
      (value "10 kOhms")
      (footprint "RES 0603_1608")
      (description "RES SMD 10K OHM 1% 1/10W 0603")
      (fields (field (name "PART NUMBER") "RT0603FRE0710KL") (field (name "MANUFACTURER") "Yageo"))
      (libsource (lib "Celestial Altium Library - altium_library") (part "Resistor"))
    )
    (comp (ref "R12")
      (value "10 kOhms")
      (footprint "RES 0603_1608")
      (description "RES SMD 10K OHM 1% 1/10W 0603")
      (fields (field (name "PART NUMBER") "RT0603FRE0710KL") (field (name "MANUFACTURER") "Yageo"))
      (libsource (lib "Celestial Altium Library - altium_library") (part "Resistor"))
    )
    (comp (ref "R13")
      (value "5.6 kOhms")
      (footprint "RES 0603_1608")
      (description "RES SMD 5.6K OHM 0.5% 1/10W 0603")
      (fields (field (name "PART NUMBER") "RT0603DRE075K6L") (field (name "MANUFACTURER") "Yageo"))
      (libsource (lib "Celestial Altium Library - altium_library") (part "Resistor"))
    )
    (comp (ref "R14")
      (value "5.6 kOhms")
      (footprint "RES 0603_1608")
      (description "RES SMD 5.6K OHM 0.5% 1/10W 0603")
      (fields (field (name "PART NUMBER") "RT0603DRE075K6L") (field (name "MANUFACTURER") "Yageo"))
      (libsource (lib "Celestial Altium Library - altium_library") (part "Resistor"))
    )
    (comp (ref "R15")
      (value "5.6 kOhms")
      (footprint "RES 0603_1608")
      (description "RES SMD 5.6K OHM 0.5% 1/10W 0603")
      (fields (field (name "PART NUMBER") "RT0603DRE075K6L") (field (name "MANUFACTURER") "Yageo"))
      (libsource (lib "Celestial Altium Library - altium_library") (part "Resistor"))
    )
    (comp (ref "R16")
      (value "5.6 kOhms")
      (footprint "RES 0603_1608")
      (description "RES SMD 5.6K OHM 0.5% 1/10W 0603")
      (fields (field (name "PART NUMBER") "RT0603DRE075K6L") (field (name "MANUFACTURER") "Yageo"))
      (libsource (lib "Celestial Altium Library - altium_library") (part "Resistor"))
    )
    (comp (ref "TP1")
      (value "UART4_TX")
      (footprint "ProtoStack_H750VBT:TESTPOINT_VIA")
      (libsource (lib "ProtoStack_H750VBT") (part "TestPoint"))
    )
    (comp (ref "TP2")
      (value "UART4_RX")
      (footprint "ProtoStack_H750VBT:TESTPOINT_VIA")
      (libsource (lib "ProtoStack_H750VBT") (part "TestPoint"))
    )
    (comp (ref "U1")
      (value "W9812G6KH-6")
      (footprint "TSOP-54")
      (libsource (lib "DAC_ADC") (part "W9812G6KH-6"))
    )
    (comp (ref "U2")
      (value "W9812G6KH-6")
      (footprint "TSOP-54")
      (libsource (lib "DAC_ADC") (part "W9812G6KH-6"))
    )
    (comp (ref "U3")
      (value "W9812G6KH-6")
      (footprint "TSOP-54")
      (libsource (lib "DAC_ADC") (part "W9812G6KH-6"))
    )
    (comp (ref "U4")
      (value "W9812G6KH-6")
      (footprint "TSOP-54")
      (libsource (lib "DAC_ADC") (part "W9812G6KH-6"))
    )
    (comp (ref "Y1")
      (value "24MHz")
      (footprint "NDK NX3225SA")
      (description "CRYSTAL 24MHZ 9PF SMD")
      (fields
        (field (name "PART NUMBER") "NX3225SA-24MHZ-EXS00A-CS07532")
        (field (name "MANUFACTURER") "NDK America, Inc.")
      )
      (libsource (lib "Celestial Altium Library - altium_library") (part "NDK Crystal NX3225SA"))
    )
    (comp (ref "Y2")
      (value "24MHz")
      (footprint "NDK NX3225SA")
      (description "CRYSTAL 24MHZ 9PF SMD")
      (fields
        (field (name "PART NUMBER") "NX3225SA-24MHZ-EXS00A-CS07532")
        (field (name "MANUFACTURER") "NDK America, Inc.")
      )
      (libsource (lib "Celestial Altium Library - altium_library") (part "NDK Crystal NX3225SA"))
    )
    (comp (ref "Y3")
      (value "ABS07-32.768KHZ-7-T")
      (footprint "ProtoStack_H750VBT:ABS07")
      (description "Crystal or Oscillator")
      (fields (field (name "MOUSER PART NUMBER") "815-ABS07-32.768K7T"))
      (libsource (lib "ProtoStack_H750VBT") (part "ABS07-32.768KHZ-7-T"))
    )
  )
  (nets
    (net (code "19") (name "+MCU") (class "Default")
      (node (ref "C11") (pin "1") (pinfunction "1_1") (pintype "passive"))
      (node (ref "C12") (pin "1") (pinfunction "1_1") (pintype "passive"))
      (node (ref "C13") (pin "1") (pinfunction "1_1") (pintype "passive"))
      (node (ref "C14") (pin "1") (pinfunction "1_1") (pintype "passive"))
      (node (ref "C15") (pin "1") (pinfunction "1_1") (pintype "passive"))
      (node (ref "C16") (pin "1") (pinfunction "1_1") (pintype "passive"))
      (node (ref "C17") (pin "1") (pinfunction "1_1") (pintype "passive"))
      (node (ref "C18") (pin "1") (pinfunction "1_1") (pintype "passive"))
      (node (ref "C19") (pin "1") (pinfunction "1_1") (pintype "passive"))
      (node (ref "C20") (pin "1") (pinfunction "1_1") (pintype "passive"))
      (node (ref "C21") (pin "1") (pinfunction "1_1") (pintype "passive"))
      (node (ref "C22") (pin "1") (pinfunction "1_1") (pintype "passive"))
      (node (ref "C23") (pin "1") (pinfunction "1_1") (pintype "passive"))
      (node (ref "C24") (pin "1") (pinfunction "1_1") (pintype "passive"))
      (node (ref "C25") (pin "1") (pinfunction "1_1") (pintype "passive"))
      (node (ref "C26") (pin "1") (pinfunction "1_1") (pintype "passive"))
      (node (ref "C27") (pin "1") (pinfunction "1_1") (pintype "passive"))
      (node (ref "C28") (pin "1") (pinfunction "1_1") (pintype "passive"))
      (node (ref "C29") (pin "1") (pinfunction "1_1") (pintype "passive"))
      (node (ref "C30") (pin "1") (pinfunction "1_1") (pintype "passive"))
      (node (ref "C31") (pin "1") (pinfunction "1_1") (pintype "passive"))
      (node (ref "C32") (pin "1") (pinfunction "1_1") (pintype "passive"))
      (node (ref "C33") (pin "1") (pinfunction "1_1") (pintype "passive"))
      (node (ref "C34") (pin "1") (pinfunction "1_1") (pintype "passive"))
      (node (ref "C35") (pin "1") (pinfunction "1_1") (pintype "passive"))
      (node (ref "C36") (pin "1") (pinfunction "1_1") (pintype "passive"))
      (node (ref "C37") (pin "1") (pinfunction "1_1") (pintype "passive"))
      (node (ref "C38") (pin "1") (pinfunction "1_1") (pintype "passive"))
      (node (ref "C39") (pin "1") (pinfunction "1_1") (pintype "passive"))
      (node (ref "C40") (pin "1") (pinfunction "1_1") (pintype "passive"))
      (node (ref "C41") (pin "1") (pinfunction "1_1") (pintype "passive"))
      (node (ref "C42") (pin "1") (pinfunction "1_1") (pintype "passive"))
      (node (ref "C43") (pin "1") (pinfunction "1_1") (pintype "passive"))
      (node (ref "C44") (pin "1") (pinfunction "1_1") (pintype "passive"))
      (node (ref "C45") (pin "1") (pinfunction "1_1") (pintype "passive"))
      (node (ref "C46") (pin "1") (pinfunction "1_1") (pintype "passive"))
      (node (ref "C47") (pin "1") (pinfunction "1_1") (pintype "passive"))
      (node (ref "C48") (pin "1") (pinfunction "1_1") (pintype "passive"))
      (node (ref "C49") (pin "1") (pinfunction "1_1") (pintype "passive"))
      (node (ref "C50") (pin "1") (pinfunction "1_1") (pintype "passive"))
      (node (ref "C51") (pin "1") (pinfunction "1_1") (pintype "passive"))
      (node (ref "C52") (pin "1") (pinfunction "1_1") (pintype "passive"))
      (node (ref "C53") (pin "1") (pinfunction "1_1") (pintype "passive"))
      (node (ref "C54") (pin "1") (pinfunction "1_1") (pintype "passive"))
      (node (ref "C55") (pin "1") (pinfunction "1_1") (pintype "passive"))
      (node (ref "C56") (pin "1") (pinfunction "1_1") (pintype "passive"))
      (node (ref "C57") (pin "1") (pinfunction "1_1") (pintype "passive"))
      (node (ref "C58") (pin "1") (pinfunction "1_1") (pintype "passive"))
      (node (ref "C59") (pin "1") (pinfunction "1_1") (pintype "passive"))
      (node (ref "C60") (pin "1") (pinfunction "1_1") (pintype "passive"))
      (node (ref "C61") (pin "2") (pinfunction "2_2") (pintype "passive"))
      (node (ref "C62") (pin "2") (pinfunction "2_2") (pintype "passive"))
      (node (ref "C63") (pin "2") (pinfunction "2_2") (pintype "passive"))
      (node (ref "C64") (pin "2") (pinfunction "2_2") (pintype "passive"))
      (node (ref "C65") (pin "2") (pinfunction "2_2") (pintype "passive"))
      (node (ref "C66") (pin "2") (pinfunction "2_2") (pintype "passive"))
      (node (ref "IC1") (pin "108") (pinfunction "VDD_8_108") (pintype "passive"))
      (node (ref "IC1") (pin "121") (pinfunction "VDD_9_121") (pintype "passive"))
      (node (ref "IC1") (pin "131") (pinfunction "VDD_10_131") (pintype "passive"))
      (node (ref "IC1") (pin "144") (pinfunction "VDD_11_144") (pintype "passive"))
      (node (ref "IC1") (pin "17") (pinfunction "VDD_1_17") (pintype "passive"))
      (node (ref "IC1") (pin "30") (pinfunction "VDD_2_30") (pintype "passive"))
      (node (ref "IC1") (pin "32") (pinfunction "VREF+_32") (pintype "passive"))
      (node (ref "IC1") (pin "33") (pinfunction "VDDA_33") (pintype "passive"))
      (node (ref "IC1") (pin "39") (pinfunction "VDD_3_39") (pintype "passive"))
      (node (ref "IC1") (pin "52") (pinfunction "VDD_4_52") (pintype "passive"))
      (node (ref "IC1") (pin "62") (pinfunction "VDD_5_62") (pintype "passive"))
      (node (ref "IC1") (pin "72") (pinfunction "VDD_6_72") (pintype "passive"))
      (node (ref "IC1") (pin "84") (pinfunction "VDD_7_84") (pintype "passive"))
      (node (ref "IC2") (pin "108") (pinfunction "VDD_8_108") (pintype "passive"))
      (node (ref "IC2") (pin "121") (pinfunction "VDD_9_121") (pintype "passive"))
      (node (ref "IC2") (pin "131") (pinfunction "VDD_10_131") (pintype "passive"))
      (node (ref "IC2") (pin "144") (pinfunction "VDD_11_144") (pintype "passive"))
      (node (ref "IC2") (pin "17") (pinfunction "VDD_1_17") (pintype "passive"))
      (node (ref "IC2") (pin "30") (pinfunction "VDD_2_30") (pintype "passive"))
      (node (ref "IC2") (pin "32") (pinfunction "VREF+_32") (pintype "passive"))
      (node (ref "IC2") (pin "33") (pinfunction "VDDA_33") (pintype "passive"))
      (node (ref "IC2") (pin "39") (pinfunction "VDD_3_39") (pintype "passive"))
      (node (ref "IC2") (pin "52") (pinfunction "VDD_4_52") (pintype "passive"))
      (node (ref "IC2") (pin "62") (pinfunction "VDD_5_62") (pintype "passive"))
      (node (ref "IC2") (pin "72") (pinfunction "VDD_6_72") (pintype "passive"))
      (node (ref "IC2") (pin "84") (pinfunction "VDD_7_84") (pintype "passive"))
      (node (ref "IC3") (pin "8") (pinfunction "VCC_8") (pintype "passive"))
      (node (ref "IC4") (pin "5") (pinfunction "VCC_5") (pintype "passive"))
      (node (ref "IC5") (pin "8") (pinfunction "VCC_8") (pintype "power_in"))
      (node (ref "IC6") (pin "8") (pinfunction "VCC_8") (pintype "power_in"))
      (node (ref "IC7") (pin "8") (pinfunction "VCC_8") (pintype "passive"))
      (node (ref "IC8") (pin "8") (pinfunction "VCC_8") (pintype "passive"))
      (node (ref "J3") (pin "16") (pinfunction "16_16") (pintype "passive"))
      (node (ref "J3") (pin "18") (pinfunction "18_18") (pintype "passive"))
      (node (ref "J3") (pin "20") (pinfunction "20_20") (pintype "passive"))
      (node (ref "J3") (pin "22") (pinfunction "22_22") (pintype "passive"))
      (node (ref "J3") (pin "24") (pinfunction "24_24") (pintype "passive"))
      (node (ref "J3") (pin "26") (pinfunction "26_26") (pintype "passive"))
      (node (ref "J4") (pin "2") (pinfunction "IN_2") (pintype "passive"))
      (node (ref "J5") (pin "1") (pinfunction "IN_1") (pintype "passive"))
      (node (ref "J6") (pin "1") (pinfunction "IN_1") (pintype "passive"))
      (node (ref "J8") (pin "2") (pinfunction "IN_2") (pintype "passive"))
      (node (ref "R13") (pin "2") (pinfunction "2_2") (pintype "passive"))
      (node (ref "R14") (pin "2") (pinfunction "2_2") (pintype "passive"))
      (node (ref "R15") (pin "2") (pinfunction "2_2") (pintype "passive"))
      (node (ref "R16") (pin "2") (pinfunction "2_2") (pintype "passive"))
      (node (ref "R5") (pin "1") (pinfunction "1_1") (pintype "passive"))
      (node (ref "R6") (pin "1") (pinfunction "1_1") (pintype "passive"))
      (node (ref "U1") (pin "1") (pinfunction "VDD_1") (pintype "passive"))
      (node (ref "U1") (pin "14") (pinfunction "VDD_14") (pintype "passive"))
      (node (ref "U1") (pin "27") (pinfunction "VDD_27") (pintype "passive"))
      (node (ref "U1") (pin "3") (pinfunction "VDDQ_3") (pintype "passive"))
      (node (ref "U1") (pin "43") (pinfunction "VDDQ_43") (pintype "passive"))
      (node (ref "U1") (pin "49") (pinfunction "VDDQ_49") (pintype "passive"))
      (node (ref "U1") (pin "9") (pinfunction "VDDQ_9") (pintype "passive"))
      (node (ref "U2") (pin "1") (pinfunction "VDD_1") (pintype "passive"))
      (node (ref "U2") (pin "14") (pinfunction "VDD_14") (pintype "passive"))
      (node (ref "U2") (pin "27") (pinfunction "VDD_27") (pintype "passive"))
      (node (ref "U2") (pin "3") (pinfunction "VDDQ_3") (pintype "passive"))
      (node (ref "U2") (pin "43") (pinfunction "VDDQ_43") (pintype "passive"))
      (node (ref "U2") (pin "49") (pinfunction "VDDQ_49") (pintype "passive"))
      (node (ref "U2") (pin "9") (pinfunction "VDDQ_9") (pintype "passive"))
      (node (ref "U3") (pin "1") (pinfunction "VDD_1") (pintype "passive"))
      (node (ref "U3") (pin "14") (pinfunction "VDD_14") (pintype "passive"))
      (node (ref "U3") (pin "27") (pinfunction "VDD_27") (pintype "passive"))
      (node (ref "U3") (pin "3") (pinfunction "VDDQ_3") (pintype "passive"))
      (node (ref "U3") (pin "43") (pinfunction "VDDQ_43") (pintype "passive"))
      (node (ref "U3") (pin "49") (pinfunction "VDDQ_49") (pintype "passive"))
      (node (ref "U3") (pin "9") (pinfunction "VDDQ_9") (pintype "passive"))
      (node (ref "U4") (pin "1") (pinfunction "VDD_1") (pintype "passive"))
      (node (ref "U4") (pin "14") (pinfunction "VDD_14") (pintype "passive"))
      (node (ref "U4") (pin "27") (pinfunction "VDD_27") (pintype "passive"))
      (node (ref "U4") (pin "3") (pinfunction "VDDQ_3") (pintype "passive"))
      (node (ref "U4") (pin "43") (pinfunction "VDDQ_43") (pintype "passive"))
      (node (ref "U4") (pin "49") (pinfunction "VDDQ_49") (pintype "passive"))
      (node (ref "U4") (pin "9") (pinfunction "VDDQ_9") (pintype "passive"))
    )
    (net (code "20") (name "/A0") (class "Default")
      (node (ref "IC1") (pin "10") (pinfunction "PF0_10") (pintype "passive"))
      (node (ref "U1") (pin "23") (pinfunction "A0_23") (pintype "passive"))
      (node (ref "U2") (pin "23") (pinfunction "A0_23") (pintype "passive"))
    )
    (net (code "21") (name "/A01") (class "Default")
      (node (ref "IC2") (pin "10") (pinfunction "PF0_10") (pintype "passive"))
      (node (ref "U3") (pin "23") (pinfunction "A0_23") (pintype "passive"))
      (node (ref "U4") (pin "23") (pinfunction "A0_23") (pintype "passive"))
    )
    (net (code "22") (name "/A1") (class "Default")
      (node (ref "IC1") (pin "11") (pinfunction "PF1_11") (pintype "passive"))
      (node (ref "U1") (pin "24") (pinfunction "A1_24") (pintype "passive"))
      (node (ref "U2") (pin "24") (pinfunction "A1_24") (pintype "passive"))
    )
    (net (code "24") (name "/A1_1") (class "Default")
      (node (ref "IC2") (pin "11") (pinfunction "PF1_11") (pintype "passive"))
      (node (ref "U3") (pin "24") (pinfunction "A1_24") (pintype "passive"))
      (node (ref "U4") (pin "24") (pinfunction "A1_24") (pintype "passive"))
    )
    (net (code "25") (name "/A2") (class "Default")
      (node (ref "IC1") (pin "12") (pinfunction "PF2_12") (pintype "passive"))
      (node (ref "U1") (pin "25") (pinfunction "A2_25") (pintype "passive"))
      (node (ref "U2") (pin "25") (pinfunction "A2_25") (pintype "passive"))
    )
    (net (code "26") (name "/A3") (class "Default")
      (node (ref "IC1") (pin "13") (pinfunction "PF3_13") (pintype "passive"))
      (node (ref "U1") (pin "26") (pinfunction "A3_26") (pintype "passive"))
      (node (ref "U2") (pin "26") (pinfunction "A3_26") (pintype "passive"))
    )
    (net (code "27") (name "/A4") (class "Default")
      (node (ref "IC1") (pin "14") (pinfunction "PF4_14") (pintype "passive"))
      (node (ref "U1") (pin "29") (pinfunction "A4_29") (pintype "passive"))
      (node (ref "U2") (pin "29") (pinfunction "A4_29") (pintype "passive"))
    )
    (net (code "28") (name "/A5") (class "Default")
      (node (ref "IC1") (pin "15") (pinfunction "PF5_15") (pintype "passive"))
      (node (ref "U1") (pin "30") (pinfunction "A5_30") (pintype "passive"))
      (node (ref "U2") (pin "30") (pinfunction "A5_30") (pintype "passive"))
    )
    (net (code "29") (name "/A6") (class "Default")
      (node (ref "IC1") (pin "50") (pinfunction "PF12_50") (pintype "passive"))
      (node (ref "U1") (pin "31") (pinfunction "A6_31") (pintype "passive"))
      (node (ref "U2") (pin "31") (pinfunction "A6_31") (pintype "passive"))
    )
    (net (code "30") (name "/A7") (class "Default")
      (node (ref "IC1") (pin "53") (pinfunction "PF13_53") (pintype "passive"))
      (node (ref "U1") (pin "32") (pinfunction "A7_32") (pintype "passive"))
      (node (ref "U2") (pin "32") (pinfunction "A7_32") (pintype "passive"))
    )
    (net (code "31") (name "/A8") (class "Default")
      (node (ref "IC1") (pin "54") (pinfunction "PF14_54") (pintype "passive"))
      (node (ref "U1") (pin "33") (pinfunction "A8_33") (pintype "passive"))
      (node (ref "U2") (pin "33") (pinfunction "A8_33") (pintype "passive"))
    )
    (net (code "32") (name "/A9") (class "Default")
      (node (ref "IC1") (pin "55") (pinfunction "PF15_55") (pintype "passive"))
      (node (ref "U1") (pin "34") (pinfunction "A9_34") (pintype "passive"))
      (node (ref "U2") (pin "34") (pinfunction "A9_34") (pintype "passive"))
    )
    (net (code "33") (name "/A10") (class "Default")
      (node (ref "IC1") (pin "56") (pinfunction "PG0_56") (pintype "passive"))
      (node (ref "U1") (pin "22") (pinfunction "A10/AP_22") (pintype "passive"))
      (node (ref "U2") (pin "22") (pinfunction "A10/AP_22") (pintype "passive"))
    )
    (net (code "34") (name "/A11") (class "Default")
      (node (ref "IC1") (pin "57") (pinfunction "PG1_57") (pintype "passive"))
      (node (ref "U1") (pin "35") (pinfunction "A11_35") (pintype "passive"))
      (node (ref "U2") (pin "35") (pinfunction "A11_35") (pintype "passive"))
    )
    (net (code "35") (name "/A21") (class "Default")
      (node (ref "IC2") (pin "12") (pinfunction "PF2_12") (pintype "passive"))
      (node (ref "U3") (pin "25") (pinfunction "A2_25") (pintype "passive"))
      (node (ref "U4") (pin "25") (pinfunction "A2_25") (pintype "passive"))
    )
    (net (code "36") (name "/A31") (class "Default")
      (node (ref "IC2") (pin "13") (pinfunction "PF3_13") (pintype "passive"))
      (node (ref "U3") (pin "26") (pinfunction "A3_26") (pintype "passive"))
      (node (ref "U4") (pin "26") (pinfunction "A3_26") (pintype "passive"))
    )
    (net (code "37") (name "/A41") (class "Default")
      (node (ref "IC2") (pin "14") (pinfunction "PF4_14") (pintype "passive"))
      (node (ref "U3") (pin "29") (pinfunction "A4_29") (pintype "passive"))
      (node (ref "U4") (pin "29") (pinfunction "A4_29") (pintype "passive"))
    )
    (net (code "38") (name "/A51") (class "Default")
      (node (ref "IC2") (pin "15") (pinfunction "PF5_15") (pintype "passive"))
      (node (ref "U3") (pin "30") (pinfunction "A5_30") (pintype "passive"))
      (node (ref "U4") (pin "30") (pinfunction "A5_30") (pintype "passive"))
    )
    (net (code "39") (name "/A61") (class "Default")
      (node (ref "IC2") (pin "50") (pinfunction "PF12_50") (pintype "passive"))
      (node (ref "U3") (pin "31") (pinfunction "A6_31") (pintype "passive"))
      (node (ref "U4") (pin "31") (pinfunction "A6_31") (pintype "passive"))
    )
    (net (code "40") (name "/A71") (class "Default")
      (node (ref "IC2") (pin "53") (pinfunction "PF13_53") (pintype "passive"))
      (node (ref "U3") (pin "32") (pinfunction "A7_32") (pintype "passive"))
      (node (ref "U4") (pin "32") (pinfunction "A7_32") (pintype "passive"))
    )
    (net (code "41") (name "/A81") (class "Default")
      (node (ref "IC2") (pin "54") (pinfunction "PF14_54") (pintype "passive"))
      (node (ref "U3") (pin "33") (pinfunction "A8_33") (pintype "passive"))
      (node (ref "U4") (pin "33") (pinfunction "A8_33") (pintype "passive"))
    )
    (net (code "42") (name "/A91") (class "Default")
      (node (ref "IC2") (pin "55") (pinfunction "PF15_55") (pintype "passive"))
      (node (ref "U3") (pin "34") (pinfunction "A9_34") (pintype "passive"))
      (node (ref "U4") (pin "34") (pinfunction "A9_34") (pintype "passive"))
    )
    (net (code "43") (name "/A101") (class "Default")
      (node (ref "IC2") (pin "56") (pinfunction "PG0_56") (pintype "passive"))
      (node (ref "U3") (pin "22") (pinfunction "A10/AP_22") (pintype "passive"))
      (node (ref "U4") (pin "22") (pinfunction "A10/AP_22") (pintype "passive"))
    )
    (net (code "44") (name "/A111") (class "Default")
      (node (ref "IC2") (pin "57") (pinfunction "PG1_57") (pintype "passive"))
      (node (ref "U3") (pin "35") (pinfunction "A11_35") (pintype "passive"))
      (node (ref "U4") (pin "35") (pinfunction "A11_35") (pintype "passive"))
    )
    (net (code "45") (name "/ADC1") (class "Default")
      (node (ref "IC1") (pin "27") (pinfunction "PC1_27") (pintype "passive"))
      (node (ref "J1") (pin "20") (pinfunction "20_20") (pintype "passive"))
    )
    (net (code "46") (name "/ADC2") (class "Default")
      (node (ref "IC1") (pin "37") (pinfunction "PA3_37") (pintype "passive"))
      (node (ref "J1") (pin "18") (pinfunction "18_18") (pintype "passive"))
    )
    (net (code "47") (name "/ADC3") (class "Default")
      (node (ref "IC1") (pin "40") (pinfunction "PA4_40") (pintype "passive"))
      (node (ref "J1") (pin "16") (pinfunction "16_16") (pintype "passive"))
    )
    (net (code "48") (name "/ADC4") (class "Default")
      (node (ref "IC1") (pin "41") (pinfunction "PA5_41") (pintype "passive"))
      (node (ref "J1") (pin "14") (pinfunction "14_14") (pintype "passive"))
    )
    (net (code "49") (name "/ADC5") (class "Default")
      (node (ref "IC1") (pin "42") (pinfunction "PA6_42") (pintype "passive"))
      (node (ref "J1") (pin "12") (pinfunction "12_12") (pintype "passive"))
    )
    (net (code "50") (name "/ADC6") (class "Default")
      (node (ref "IC1") (pin "43") (pinfunction "PA7_43") (pintype "passive"))
      (node (ref "J1") (pin "10") (pinfunction "10_10") (pintype "passive"))
    )
    (net (code "51") (name "/ADC7") (class "Default")
      (node (ref "IC1") (pin "44") (pinfunction "PC4_44") (pintype "passive"))
      (node (ref "J1") (pin "8") (pinfunction "8_8") (pintype "passive"))
    )
    (net (code "52") (name "/ADC8") (class "Default")
      (node (ref "IC1") (pin "45") (pinfunction "PC5_45") (pintype "passive"))
      (node (ref "J1") (pin "6") (pinfunction "6_6") (pintype "passive"))
    )
    (net (code "53") (name "/ADC9") (class "Default")
      (node (ref "IC1") (pin "46") (pinfunction "PB0_46") (pintype "passive"))
      (node (ref "J1") (pin "4") (pinfunction "4_4") (pintype "passive"))
    )
    (net (code "54") (name "/ADC10") (class "Default")
      (node (ref "IC1") (pin "47") (pinfunction "PB1_47") (pintype "passive"))
      (node (ref "J1") (pin "2") (pinfunction "2_2") (pintype "passive"))
    )
    (net (code "56") (name "/AUDIO_NRST") (class "Default")
      (node (ref "C8") (pin "2") (pinfunction "2_2") (pintype "passive"))
      (node (ref "IC2") (pin "25") (pinfunction "NRST_25") (pintype "passive"))
      (node (ref "J3") (pin "2") (pinfunction "2_2") (pintype "passive"))
      (node (ref "R6") (pin "2") (pinfunction "2_2") (pintype "passive"))
    )
    (net (code "58") (name "/BA0") (class "Default")
      (node (ref "IC1") (pin "89") (pinfunction "PG4_89") (pintype "passive"))
      (node (ref "U1") (pin "20") (pinfunction "BS0_20") (pintype "passive"))
      (node (ref "U2") (pin "20") (pinfunction "BS0_20") (pintype "passive"))
    )
    (net (code "59") (name "/BA01") (class "Default")
      (node (ref "IC2") (pin "89") (pinfunction "PG4_89") (pintype "passive"))
      (node (ref "U3") (pin "20") (pinfunction "BS0_20") (pintype "passive"))
      (node (ref "U4") (pin "20") (pinfunction "BS0_20") (pintype "passive"))
    )
    (net (code "60") (name "/BA1") (class "Default")
      (node (ref "IC1") (pin "90") (pinfunction "PG5_90") (pintype "passive"))
      (node (ref "U1") (pin "21") (pinfunction "BS1_21") (pintype "passive"))
      (node (ref "U2") (pin "21") (pinfunction "BS1_21") (pintype "passive"))
    )
    (net (code "61") (name "/BA11") (class "Default")
      (node (ref "IC2") (pin "90") (pinfunction "PG5_90") (pintype "passive"))
      (node (ref "U3") (pin "21") (pinfunction "BS1_21") (pintype "passive"))
      (node (ref "U4") (pin "21") (pinfunction "BS1_21") (pintype "passive"))
    )
    (net (code "62") (name "/CODEC_GPIO") (class "Default")
      (node (ref "IC2") (pin "7") (pinfunction "PC13_7") (pintype "passive"))
      (node (ref "J3") (pin "1") (pinfunction "1_1") (pintype "passive"))
    )
    (net (code "63") (name "/D0") (class "Default")
      (node (ref "IC1") (pin "85") (pinfunction "PD14_85") (pintype "passive"))
      (node (ref "J1") (pin "41") (pinfunction "41_41") (pintype "passive"))
      (node (ref "U1") (pin "2") (pinfunction "DQ0_2") (pintype "passive"))
      (node (ref "U2") (pin "2") (pinfunction "DQ0_2") (pintype "passive"))
    )
    (net (code "64") (name "/D1") (class "Default")
      (node (ref "IC1") (pin "86") (pinfunction "PD15_86") (pintype "passive"))
      (node (ref "J1") (pin "39") (pinfunction "39_39") (pintype "passive"))
      (node (ref "U1") (pin "4") (pinfunction "DQ1_4") (pintype "passive"))
      (node (ref "U2") (pin "4") (pinfunction "DQ1_4") (pintype "passive"))
    )
    (net (code "65") (name "/D01") (class "Default")
      (node (ref "IC2") (pin "85") (pinfunction "PD14_85") (pintype "passive"))
      (node (ref "U3") (pin "2") (pinfunction "DQ0_2") (pintype "passive"))
      (node (ref "U4") (pin "2") (pinfunction "DQ0_2") (pintype "passive"))
    )
    (net (code "67") (name "/D1_1") (class "Default")
      (node (ref "IC2") (pin "86") (pinfunction "PD15_86") (pintype "passive"))
      (node (ref "U3") (pin "4") (pinfunction "DQ1_4") (pintype "passive"))
      (node (ref "U4") (pin "4") (pinfunction "DQ1_4") (pintype "passive"))
    )
    (net (code "68") (name "/D2") (class "Default")
      (node (ref "IC1") (pin "114") (pinfunction "PD0_114") (pintype "passive"))
      (node (ref "J1") (pin "37") (pinfunction "37_37") (pintype "passive"))
      (node (ref "U1") (pin "5") (pinfunction "DQ2_5") (pintype "passive"))
      (node (ref "U2") (pin "5") (pinfunction "DQ2_5") (pintype "passive"))
    )
    (net (code "69") (name "/D3") (class "Default")
      (node (ref "IC1") (pin "115") (pinfunction "PD1_115") (pintype "passive"))
      (node (ref "J1") (pin "35") (pinfunction "35_35") (pintype "passive"))
      (node (ref "U1") (pin "7") (pinfunction "DQ3_7") (pintype "passive"))
      (node (ref "U2") (pin "7") (pinfunction "DQ3_7") (pintype "passive"))
    )
    (net (code "70") (name "/D4") (class "Default")
      (node (ref "IC1") (pin "58") (pinfunction "PE7_58") (pintype "passive"))
      (node (ref "J1") (pin "33") (pinfunction "33_33") (pintype "passive"))
      (node (ref "U1") (pin "8") (pinfunction "DQ4_8") (pintype "passive"))
      (node (ref "U2") (pin "8") (pinfunction "DQ4_8") (pintype "passive"))
    )
    (net (code "71") (name "/D5") (class "Default")
      (node (ref "IC1") (pin "59") (pinfunction "PE8_59") (pintype "passive"))
      (node (ref "J1") (pin "31") (pinfunction "31_31") (pintype "passive"))
      (node (ref "U1") (pin "10") (pinfunction "DQ5_10") (pintype "passive"))
      (node (ref "U2") (pin "10") (pinfunction "DQ5_10") (pintype "passive"))
    )
    (net (code "72") (name "/D6") (class "Default")
      (node (ref "IC1") (pin "60") (pinfunction "PE9_60") (pintype "passive"))
      (node (ref "J1") (pin "29") (pinfunction "29_29") (pintype "passive"))
      (node (ref "U1") (pin "11") (pinfunction "DQ6_11") (pintype "passive"))
      (node (ref "U2") (pin "11") (pinfunction "DQ6_11") (pintype "passive"))
    )
    (net (code "73") (name "/D7") (class "Default")
      (node (ref "IC1") (pin "63") (pinfunction "PE10_63") (pintype "passive"))
      (node (ref "J1") (pin "27") (pinfunction "27_27") (pintype "passive"))
      (node (ref "U1") (pin "13") (pinfunction "DQ7_13") (pintype "passive"))
      (node (ref "U2") (pin "13") (pinfunction "DQ7_13") (pintype "passive"))
    )
    (net (code "74") (name "/D8") (class "Default")
      (node (ref "IC1") (pin "64") (pinfunction "PE11_64") (pintype "passive"))
      (node (ref "J1") (pin "15") (pinfunction "15_15") (pintype "passive"))
      (node (ref "U1") (pin "42") (pinfunction "DQ8_42") (pintype "passive"))
      (node (ref "U2") (pin "42") (pinfunction "DQ8_42") (pintype "passive"))
    )
    (net (code "75") (name "/D9") (class "Default")
      (node (ref "IC1") (pin "65") (pinfunction "PE12_65") (pintype "passive"))
      (node (ref "J1") (pin "13") (pinfunction "13_13") (pintype "passive"))
      (node (ref "U1") (pin "44") (pinfunction "DQ9_44") (pintype "passive"))
      (node (ref "U2") (pin "44") (pinfunction "DQ9_44") (pintype "passive"))
    )
    (net (code "76") (name "/D10") (class "Default")
      (node (ref "IC1") (pin "66") (pinfunction "PE13_66") (pintype "passive"))
      (node (ref "J1") (pin "11") (pinfunction "11_11") (pintype "passive"))
      (node (ref "U1") (pin "45") (pinfunction "DQ10_45") (pintype "passive"))
      (node (ref "U2") (pin "45") (pinfunction "DQ10_45") (pintype "passive"))
    )
    (net (code "77") (name "/D11") (class "Default")
      (node (ref "IC1") (pin "67") (pinfunction "PE14_67") (pintype "passive"))
      (node (ref "J1") (pin "9") (pinfunction "9_9") (pintype "passive"))
      (node (ref "U1") (pin "47") (pinfunction "DQ11_47") (pintype "passive"))
      (node (ref "U2") (pin "47") (pinfunction "DQ11_47") (pintype "passive"))
    )
    (net (code "78") (name "/D12") (class "Default")
      (node (ref "IC1") (pin "68") (pinfunction "PE15_68") (pintype "passive"))
      (node (ref "J1") (pin "7") (pinfunction "7_7") (pintype "passive"))
      (node (ref "U1") (pin "48") (pinfunction "DQ12_48") (pintype "passive"))
      (node (ref "U2") (pin "48") (pinfunction "DQ12_48") (pintype "passive"))
    )
    (net (code "79") (name "/D13") (class "Default")
      (node (ref "IC1") (pin "77") (pinfunction "PD8_77") (pintype "passive"))
      (node (ref "J1") (pin "5") (pinfunction "5_5") (pintype "passive"))
      (node (ref "U1") (pin "50") (pinfunction "DQ13_50") (pintype "passive"))
      (node (ref "U2") (pin "50") (pinfunction "DQ13_50") (pintype "passive"))
    )
    (net (code "80") (name "/D14") (class "Default")
      (node (ref "IC1") (pin "78") (pinfunction "PD9_78") (pintype "passive"))
      (node (ref "J1") (pin "3") (pinfunction "3_3") (pintype "passive"))
      (node (ref "U1") (pin "51") (pinfunction "DQ14_51") (pintype "passive"))
      (node (ref "U2") (pin "51") (pinfunction "DQ14_51") (pintype "passive"))
    )
    (net (code "81") (name "/D15") (class "Default")
      (node (ref "IC1") (pin "79") (pinfunction "PD10_79") (pintype "passive"))
      (node (ref "J1") (pin "1") (pinfunction "1_1") (pintype "passive"))
      (node (ref "U1") (pin "53") (pinfunction "DQ15_53") (pintype "passive"))
      (node (ref "U2") (pin "53") (pinfunction "DQ15_53") (pintype "passive"))
    )
    (net (code "82") (name "/D21") (class "Default")
      (node (ref "IC2") (pin "114") (pinfunction "PD0_114") (pintype "passive"))
      (node (ref "U3") (pin "5") (pinfunction "DQ2_5") (pintype "passive"))
      (node (ref "U4") (pin "5") (pinfunction "DQ2_5") (pintype "passive"))
    )
    (net (code "83") (name "/D31") (class "Default")
      (node (ref "IC2") (pin "115") (pinfunction "PD1_115") (pintype "passive"))
      (node (ref "U3") (pin "7") (pinfunction "DQ3_7") (pintype "passive"))
      (node (ref "U4") (pin "7") (pinfunction "DQ3_7") (pintype "passive"))
    )
    (net (code "84") (name "/D41") (class "Default")
      (node (ref "IC2") (pin "58") (pinfunction "PE7_58") (pintype "passive"))
      (node (ref "U3") (pin "8") (pinfunction "DQ4_8") (pintype "passive"))
      (node (ref "U4") (pin "8") (pinfunction "DQ4_8") (pintype "passive"))
    )
    (net (code "85") (name "/D51") (class "Default")
      (node (ref "IC2") (pin "59") (pinfunction "PE8_59") (pintype "passive"))
      (node (ref "U3") (pin "10") (pinfunction "DQ5_10") (pintype "passive"))
      (node (ref "U4") (pin "10") (pinfunction "DQ5_10") (pintype "passive"))
    )
    (net (code "86") (name "/D61") (class "Default")
      (node (ref "IC2") (pin "60") (pinfunction "PE9_60") (pintype "passive"))
      (node (ref "U3") (pin "11") (pinfunction "DQ6_11") (pintype "passive"))
      (node (ref "U4") (pin "11") (pinfunction "DQ6_11") (pintype "passive"))
    )
    (net (code "87") (name "/D71") (class "Default")
      (node (ref "IC2") (pin "63") (pinfunction "PE10_63") (pintype "passive"))
      (node (ref "U3") (pin "13") (pinfunction "DQ7_13") (pintype "passive"))
      (node (ref "U4") (pin "13") (pinfunction "DQ7_13") (pintype "passive"))
    )
    (net (code "88") (name "/D81") (class "Default")
      (node (ref "IC2") (pin "64") (pinfunction "PE11_64") (pintype "passive"))
      (node (ref "U3") (pin "42") (pinfunction "DQ8_42") (pintype "passive"))
      (node (ref "U4") (pin "42") (pinfunction "DQ8_42") (pintype "passive"))
    )
    (net (code "89") (name "/D91") (class "Default")
      (node (ref "IC2") (pin "65") (pinfunction "PE12_65") (pintype "passive"))
      (node (ref "U3") (pin "44") (pinfunction "DQ9_44") (pintype "passive"))
      (node (ref "U4") (pin "44") (pinfunction "DQ9_44") (pintype "passive"))
    )
    (net (code "90") (name "/D101") (class "Default")
      (node (ref "IC2") (pin "66") (pinfunction "PE13_66") (pintype "passive"))
      (node (ref "U3") (pin "45") (pinfunction "DQ10_45") (pintype "passive"))
      (node (ref "U4") (pin "45") (pinfunction "DQ10_45") (pintype "passive"))
    )
    (net (code "91") (name "/D111") (class "Default")
      (node (ref "IC2") (pin "67") (pinfunction "PE14_67") (pintype "passive"))
      (node (ref "U3") (pin "47") (pinfunction "DQ11_47") (pintype "passive"))
      (node (ref "U4") (pin "47") (pinfunction "DQ11_47") (pintype "passive"))
    )
    (net (code "92") (name "/D121") (class "Default")
      (node (ref "IC2") (pin "68") (pinfunction "PE15_68") (pintype "passive"))
      (node (ref "U3") (pin "48") (pinfunction "DQ12_48") (pintype "passive"))
      (node (ref "U4") (pin "48") (pinfunction "DQ12_48") (pintype "passive"))
    )
    (net (code "93") (name "/D131") (class "Default")
      (node (ref "IC2") (pin "77") (pinfunction "PD8_77") (pintype "passive"))
      (node (ref "U3") (pin "50") (pinfunction "DQ13_50") (pintype "passive"))
      (node (ref "U4") (pin "50") (pinfunction "DQ13_50") (pintype "passive"))
    )
    (net (code "94") (name "/D141") (class "Default")
      (node (ref "IC2") (pin "78") (pinfunction "PD9_78") (pintype "passive"))
      (node (ref "U3") (pin "51") (pinfunction "DQ14_51") (pintype "passive"))
      (node (ref "U4") (pin "51") (pinfunction "DQ14_51") (pintype "passive"))
    )
    (net (code "95") (name "/D151") (class "Default")
      (node (ref "IC2") (pin "79") (pinfunction "PD10_79") (pintype "passive"))
      (node (ref "U3") (pin "53") (pinfunction "DQ15_53") (pintype "passive"))
      (node (ref "U4") (pin "53") (pinfunction "DQ15_53") (pintype "passive"))
    )
    (net (code "97") (name "/EEPROM1_SCL") (class "Default")
      (node (ref "IC2") (pin "81") (pinfunction "PD12_81") (pintype "passive"))
      (node (ref "IC8") (pin "6") (pinfunction "SCL_6") (pintype "passive"))
      (node (ref "R15") (pin "1") (pinfunction "1_1") (pintype "passive"))
    )
    (net (code "98") (name "/EEPROM1_SDA") (class "Default")
      (node (ref "IC2") (pin "82") (pinfunction "PD13_82") (pintype "passive"))
      (node (ref "IC8") (pin "5") (pinfunction "SDA_5") (pintype "passive"))
      (node (ref "R16") (pin "1") (pinfunction "1_1") (pintype "passive"))
    )
    (net (code "99") (name "/FLASH1_CLK") (class "Default")
      (node (ref "IC2") (pin "22") (pinfunction "PF10_22") (pintype "passive"))
      (node (ref "IC6") (pin "6") (pinfunction "C_6") (pintype "input"))
    )
    (net (code "100") (name "/FLASH1_CS") (class "Default")
      (node (ref "IC2") (pin "91") (pinfunction "PG6_91") (pintype "passive"))
      (node (ref "IC6") (pin "1") (pinfunction "S#_1") (pintype "input"))
    )
    (net (code "101") (name "/FLASH1_D0") (class "Default")
      (node (ref "IC2") (pin "20") (pinfunction "PF8_20") (pintype "passive"))
      (node (ref "IC6") (pin "5") (pinfunction "DQ0_5") (pintype "input"))
    )
    (net (code "102") (name "/FLASH1_D1") (class "Default")
      (node (ref "IC2") (pin "21") (pinfunction "PF9_21") (pintype "passive"))
      (node (ref "IC6") (pin "2") (pinfunction "DQ1_2") (pintype "output"))
    )
    (net (code "103") (name "/FLASH1_D2") (class "Default")
      (node (ref "IC2") (pin "19") (pinfunction "PF7_19") (pintype "passive"))
      (node (ref "IC6") (pin "3") (pinfunction "W#/VPP/DQ2_3") (pintype "passive"))
      (node (ref "J8") (pin "1") (pinfunction "IN_1") (pintype "passive"))
    )
    (net (code "104") (name "/FLASH1_D3") (class "Default")
      (node (ref "IC2") (pin "35") (pinfunction "PA1_35") (pintype "passive"))
      (node (ref "IC6") (pin "7") (pinfunction "HOLD#/DQ3_7") (pintype "passive"))
      (node (ref "J8") (pin "3") (pinfunction "IN_3") (pintype "passive"))
    )
    (net (code "105") (name "/FLASH_CLK") (class "Default")
      (node (ref "IC1") (pin "22") (pinfunction "PF10_22") (pintype "passive"))
      (node (ref "IC5") (pin "6") (pinfunction "C_6") (pintype "input"))
    )
    (net (code "106") (name "/FLASH_CS") (class "Default")
      (node (ref "IC1") (pin "91") (pinfunction "PG6_91") (pintype "passive"))
      (node (ref "IC5") (pin "1") (pinfunction "S#_1") (pintype "input"))
    )
    (net (code "107") (name "/FLASH_D0") (class "Default")
      (node (ref "IC1") (pin "80") (pinfunction "PD11_80") (pintype "passive"))
      (node (ref "IC5") (pin "5") (pinfunction "DQ0_5") (pintype "input"))
    )
    (net (code "108") (name "/FLASH_D1") (class "Default")
      (node (ref "IC1") (pin "81") (pinfunction "PD12_81") (pintype "passive"))
      (node (ref "IC5") (pin "2") (pinfunction "DQ1_2") (pintype "output"))
    )
    (net (code "109") (name "/FLASH_D2") (class "Default")
      (node (ref "IC1") (pin "1") (pinfunction "PE2_1") (pintype "passive"))
      (node (ref "IC5") (pin "3") (pinfunction "W#/VPP/DQ2_3") (pintype "passive"))
    )
    (net (code "110") (name "/FLASH_D3") (class "Default")
      (node (ref "IC1") (pin "82") (pinfunction "PD13_82") (pintype "passive"))
      (node (ref "IC5") (pin "7") (pinfunction "HOLD#/DQ3_7") (pintype "passive"))
    )
    (net (code "111") (name "/FMC_A21_RS") (class "Default")
      (node (ref "IC1") (pin "4") (pinfunction "PE5_4") (pintype "passive"))
      (node (ref "J1") (pin "17") (pinfunction "17_17") (pintype "passive"))
    )
    (net (code "112") (name "/FMC_A22_RS") (class "Default")
      (node (ref "IC1") (pin "5") (pinfunction "PE6_5") (pintype "passive"))
      (node (ref "J1") (pin "19") (pinfunction "19_19") (pintype "passive"))
    )
    (net (code "113") (name "/FMC_NE1_CS") (class "Default")
      (node (ref "IC1") (pin "97") (pinfunction "PC7_97") (pintype "passive"))
      (node (ref "J1") (pin "24") (pinfunction "24_24") (pintype "passive"))
    )
    (net (code "114") (name "/FMC_NE4_CS") (class "Default")
      (node (ref "IC1") (pin "127") (pinfunction "PG12_127") (pintype "passive"))
      (node (ref "J1") (pin "21") (pinfunction "21_21") (pintype "passive"))
    )
    (net (code "115") (name "/FMC_NOE_RD") (class "Default")
      (node (ref "IC1") (pin "118") (pinfunction "PD4_118") (pintype "passive"))
      (node (ref "J1") (pin "25") (pinfunction "25_25") (pintype "passive"))
    )
    (net (code "116") (name "/FMC_NWE_WE") (class "Default")
      (node (ref "IC1") (pin "119") (pinfunction "PD5_119") (pintype "passive"))
      (node (ref "J1") (pin "23") (pinfunction "23_23") (pintype "passive"))
    )
    (net (code "117") (name "/GUI_NRST") (class "Default")
      (node (ref "C7") (pin "2") (pinfunction "2_2") (pintype "passive"))
      (node (ref "IC1") (pin "25") (pinfunction "NRST_25") (pintype "passive"))
      (node (ref "J3") (pin "4") (pinfunction "4_4") (pintype "passive"))
      (node (ref "R5") (pin "2") (pinfunction "2_2") (pintype "passive"))
    )
    (net (code "118") (name "/GUI_PB2") (class "Default")
      (node (ref "IC1") (pin "48") (pinfunction "PB2_48") (pintype "passive"))
      (node (ref "J1") (pin "26") (pinfunction "26_26") (pintype "passive"))
    )
    (net (code "119") (name "/I2C2_SCL") (class "Default")
      (node (ref "IC1") (pin "69") (pinfunction "PB10_69") (pintype "passive"))
      (node (ref "J1") (pin "38") (pinfunction "38_38") (pintype "passive"))
    )
    (net (code "120") (name "/I2C2_SDA") (class "Default")
      (node (ref "IC1") (pin "70") (pinfunction "PB11_70") (pintype "passive"))
      (node (ref "J1") (pin "36") (pinfunction "36_36") (pintype "passive"))
    )
    (net (code "121") (name "/I2C4_SCL") (class "Default")
      (node (ref "IC1") (pin "139") (pinfunction "PB8_139") (pintype "passive"))
      (node (ref "IC7") (pin "6") (pinfunction "SCL_6") (pintype "passive"))
      (node (ref "R13") (pin "1") (pinfunction "1_1") (pintype "passive"))
    )
    (net (code "122") (name "/I2C4_SDA") (class "Default")
      (node (ref "IC1") (pin "140") (pinfunction "PB9_140") (pintype "passive"))
      (node (ref "IC7") (pin "5") (pinfunction "SDA_5") (pintype "passive"))
      (node (ref "R14") (pin "1") (pinfunction "1_1") (pintype "passive"))
    )
    (net (code "123") (name "/JTAG_JTDI") (class "Default")
      (node (ref "IC1") (pin "110") (pinfunction "PA15_110") (pintype "passive"))
      (node (ref "IC2") (pin "110") (pinfunction "PA15_110") (pintype "passive"))
      (node (ref "J3") (pin "10") (pinfunction "10_10") (pintype "passive"))
    )
    (net (code "124") (name "/JTAG_RST") (class "Default")
      (node (ref "IC1") (pin "134") (pinfunction "PB4_134") (pintype "passive"))
      (node (ref "IC2") (pin "134") (pinfunction "PB4_134") (pintype "passive"))
      (node (ref "J3") (pin "6") (pinfunction "6_6") (pintype "passive"))
    )
    (net (code "125") (name "/JTAG_SWCLK") (class "Default")
      (node (ref "IC1") (pin "109") (pinfunction "PA14_109") (pintype "passive"))
      (node (ref "IC2") (pin "109") (pinfunction "PA14_109") (pintype "passive"))
      (node (ref "J3") (pin "12") (pinfunction "12_12") (pintype "passive"))
    )
    (net (code "126") (name "/JTAG_SWDIO") (class "Default")
      (node (ref "IC1") (pin "105") (pinfunction "PA13_105") (pintype "passive"))
      (node (ref "IC2") (pin "105") (pinfunction "PA13_105") (pintype "passive"))
      (node (ref "J3") (pin "14") (pinfunction "14_14") (pintype "passive"))
    )
    (net (code "127") (name "/JTAG_SWO") (class "Default")
      (node (ref "IC1") (pin "133") (pinfunction "PB3_133") (pintype "passive"))
      (node (ref "IC2") (pin "133") (pinfunction "PB3_133") (pintype "passive"))
      (node (ref "J3") (pin "8") (pinfunction "8_8") (pintype "passive"))
    )
    (net (code "128") (name "/LCD_RESET") (class "Default")
      (node (ref "IC1") (pin "96") (pinfunction "PC6_96") (pintype "passive"))
      (node (ref "J1") (pin "22") (pinfunction "22_22") (pintype "passive"))
    )
    (net (code "129") (name "/LDQM") (class "Default")
      (node (ref "IC1") (pin "141") (pinfunction "PE0_141") (pintype "passive"))
      (node (ref "R7") (pin "2") (pinfunction "2_2") (pintype "passive"))
      (node (ref "U1") (pin "15") (pinfunction "LDQM_15") (pintype "passive"))
      (node (ref "U2") (pin "15") (pinfunction "LDQM_15") (pintype "passive"))
    )
    (net (code "130") (name "/LDQM1") (class "Default")
      (node (ref "IC2") (pin "141") (pinfunction "PE0_141") (pintype "passive"))
      (node (ref "R9") (pin "2") (pinfunction "2_2") (pintype "passive"))
      (node (ref "U3") (pin "15") (pinfunction "LDQM_15") (pintype "passive"))
      (node (ref "U4") (pin "15") (pinfunction "LDQM_15") (pintype "passive"))
    )
    (net (code "131") (name "/PSRAM1_CLK") (class "Default")
      (node (ref "IC2") (pin "74") (pinfunction "PB13_74") (pintype "passive"))
      (node (ref "IC3") (pin "6") (pinfunction "SCLK_6") (pintype "passive"))
    )
    (net (code "132") (name "/PSRAM1_CS") (class "Default")
      (node (ref "IC2") (pin "73") (pinfunction "PB12_73") (pintype "passive"))
      (node (ref "IC3") (pin "1") (pinfunction "CE#_1") (pintype "passive"))
    )
    (net (code "133") (name "/PSRAM1_MISO") (class "Default")
      (node (ref "IC2") (pin "75") (pinfunction "PB14_75") (pintype "passive"))
      (node (ref "IC3") (pin "2") (pinfunction "SO/SIO[1]_2") (pintype "passive"))
    )
    (net (code "134") (name "/PSRAM1_MOSI") (class "Default")
      (node (ref "IC2") (pin "76") (pinfunction "PB15_76") (pintype "passive"))
      (node (ref "IC3") (pin "5") (pinfunction "SI/SIO[0]_5") (pintype "passive"))
    )
    (net (code "135") (name "/SAI1_FS") (class "Default")
      (node (ref "IC2") (pin "3") (pinfunction "PE4_3") (pintype "passive"))
      (node (ref "J3") (pin "11") (pinfunction "11_11") (pintype "passive"))
    )
    (net (code "136") (name "/SAI1_MCLK") (class "Default")
      (node (ref "IC2") (pin "1") (pinfunction "PE2_1") (pintype "passive"))
      (node (ref "J3") (pin "15") (pinfunction "15_15") (pintype "passive"))
    )
    (net (code "137") (name "/SAI1_SCK") (class "Default")
      (node (ref "IC2") (pin "4") (pinfunction "PE5_4") (pintype "passive"))
      (node (ref "J3") (pin "9") (pinfunction "9_9") (pintype "passive"))
    )
    (net (code "138") (name "/SAI1_SD_A") (class "Default")
      (node (ref "IC2") (pin "5") (pinfunction "PE6_5") (pintype "passive"))
      (node (ref "J3") (pin "7") (pinfunction "7_7") (pintype "passive"))
    )
    (net (code "139") (name "/SAI1_SD_B") (class "Default")
      (node (ref "IC2") (pin "2") (pinfunction "PE3_2") (pintype "passive"))
      (node (ref "J3") (pin "13") (pinfunction "13_13") (pintype "passive"))
    )
    (net (code "140") (name "/SAI4_SD_A") (class "Default")
      (node (ref "IC2") (pin "27") (pinfunction "PC1_27") (pintype "passive"))
      (node (ref "J3") (pin "3") (pinfunction "3_3") (pintype "passive"))
    )
    (net (code "141") (name "/SAI4_SD_B") (class "Default")
      (node (ref "IC2") (pin "18") (pinfunction "PF6_18") (pintype "passive"))
      (node (ref "J3") (pin "5") (pinfunction "5_5") (pintype "passive"))
    )
    (net (code "142") (name "/SDCKE_0") (class "Default")
      (node (ref "IC1") (pin "29") (pinfunction "PC3_C_29") (pintype "passive"))
      (node (ref "U1") (pin "37") (pinfunction "CKE_37") (pintype "passive"))
    )
    (net (code "143") (name "/SDCKE_01") (class "Default")
      (node (ref "IC2") (pin "29") (pinfunction "PC3_C_29") (pintype "passive"))
      (node (ref "U3") (pin "37") (pinfunction "CKE_37") (pintype "passive"))
    )
    (net (code "144") (name "/SDCKE_1") (class "Default")
      (node (ref "IC1") (pin "135") (pinfunction "PB5_135") (pintype "passive"))
      (node (ref "U2") (pin "37") (pinfunction "CKE_37") (pintype "passive"))
    )
    (net (code "145") (name "/SDCKE_11") (class "Default")
      (node (ref "IC2") (pin "135") (pinfunction "PB5_135") (pintype "passive"))
      (node (ref "U4") (pin "37") (pinfunction "CKE_37") (pintype "passive"))
    )
    (net (code "146") (name "/SDCLK") (class "Default")
      (node (ref "IC1") (pin "93") (pinfunction "PG8_93") (pintype "passive"))
      (node (ref "U1") (pin "38") (pinfunction "CLK_38") (pintype "passive"))
      (node (ref "U2") (pin "38") (pinfunction "CLK_38") (pintype "passive"))
    )
    (net (code "147") (name "/SDCLK1") (class "Default")
      (node (ref "IC2") (pin "93") (pinfunction "PG8_93") (pintype "passive"))
      (node (ref "U3") (pin "38") (pinfunction "CLK_38") (pintype "passive"))
      (node (ref "U4") (pin "38") (pinfunction "CLK_38") (pintype "passive"))
    )
    (net (code "148") (name "/SDNCAS") (class "Default")
      (node (ref "IC1") (pin "132") (pinfunction "PG15_132") (pintype "passive"))
      (node (ref "U1") (pin "17") (pinfunction "NCAS_17") (pintype "passive"))
      (node (ref "U2") (pin "17") (pinfunction "NCAS_17") (pintype "passive"))
    )
    (net (code "149") (name "/SDNCAS1") (class "Default")
      (node (ref "IC2") (pin "132") (pinfunction "PG15_132") (pintype "passive"))
      (node (ref "U3") (pin "17") (pinfunction "NCAS_17") (pintype "passive"))
      (node (ref "U4") (pin "17") (pinfunction "NCAS_17") (pintype "passive"))
    )
    (net (code "150") (name "/SDNE_0") (class "Default")
      (node (ref "IC1") (pin "28") (pinfunction "PC2_C_28") (pintype "passive"))
      (node (ref "U1") (pin "19") (pinfunction "NCS_19") (pintype "passive"))
    )
    (net (code "151") (name "/SDNE_01") (class "Default")
      (node (ref "IC2") (pin "44") (pinfunction "PC4_44") (pintype "passive"))
      (node (ref "U3") (pin "19") (pinfunction "NCS_19") (pintype "passive"))
    )
    (net (code "152") (name "/SDNE_1") (class "Default")
      (node (ref "IC1") (pin "136") (pinfunction "PB6_136") (pintype "passive"))
      (node (ref "U2") (pin "19") (pinfunction "NCS_19") (pintype "passive"))
    )
    (net (code "153") (name "/SDNE_11") (class "Default")
      (node (ref "IC2") (pin "136") (pinfunction "PB6_136") (pintype "passive"))
      (node (ref "U4") (pin "19") (pinfunction "NCS_19") (pintype "passive"))
    )
    (net (code "154") (name "/SDNRAS") (class "Default")
      (node (ref "IC1") (pin "49") (pinfunction "PF11_49") (pintype "passive"))
      (node (ref "U1") (pin "18") (pinfunction "NRAS_18") (pintype "passive"))
      (node (ref "U2") (pin "18") (pinfunction "NRAS_18") (pintype "passive"))
    )
    (net (code "155") (name "/SDNRAS1") (class "Default")
      (node (ref "IC2") (pin "49") (pinfunction "PF11_49") (pintype "passive"))
      (node (ref "U3") (pin "18") (pinfunction "NRAS_18") (pintype "passive"))
      (node (ref "U4") (pin "18") (pinfunction "NRAS_18") (pintype "passive"))
    )
    (net (code "156") (name "/SDNWE") (class "Default")
      (node (ref "IC1") (pin "26") (pinfunction "PC0_26") (pintype "passive"))
      (node (ref "U1") (pin "16") (pinfunction "NWE_16") (pintype "passive"))
      (node (ref "U2") (pin "16") (pinfunction "NWE_16") (pintype "passive"))
    )
    (net (code "157") (name "/SDNWE1") (class "Default")
      (node (ref "IC2") (pin "43") (pinfunction "PA7_43") (pintype "passive"))
      (node (ref "U3") (pin "16") (pinfunction "NWE_16") (pintype "passive"))
      (node (ref "U4") (pin "16") (pinfunction "NWE_16") (pintype "passive"))
    )
    (net (code "158") (name "/SD_CK") (class "Default")
      (node (ref "IC1") (pin "113") (pinfunction "PC12_113") (pintype "passive"))
      (node (ref "J3") (pin "39") (pinfunction "39_39") (pintype "passive"))
    )
    (net (code "159") (name "/SD_CMD") (class "Default")
      (node (ref "IC1") (pin "116") (pinfunction "PD2_116") (pintype "passive"))
      (node (ref "J3") (pin "41") (pinfunction "41_41") (pintype "passive"))
    )
    (net (code "160") (name "/SD_D0") (class "Default")
      (node (ref "IC1") (pin "98") (pinfunction "PC8_98") (pintype "passive"))
      (node (ref "J3") (pin "31") (pinfunction "31_31") (pintype "passive"))
    )
    (net (code "161") (name "/SD_D1") (class "Default")
      (node (ref "IC1") (pin "99") (pinfunction "PC9_99") (pintype "passive"))
      (node (ref "J3") (pin "33") (pinfunction "33_33") (pintype "passive"))
    )
    (net (code "162") (name "/SD_D2") (class "Default")
      (node (ref "IC1") (pin "111") (pinfunction "PC10_111") (pintype "passive"))
      (node (ref "J3") (pin "35") (pinfunction "35_35") (pintype "passive"))
    )
    (net (code "163") (name "/SD_D3") (class "Default")
      (node (ref "IC1") (pin "112") (pinfunction "PC11_112") (pintype "passive"))
      (node (ref "J3") (pin "37") (pinfunction "37_37") (pintype "passive"))
    )
    (net (code "164") (name "/SD_DETECT") (class "Default")
      (node (ref "IC1") (pin "102") (pinfunction "PA10_102") (pintype "passive"))
      (node (ref "J3") (pin "29") (pinfunction "29_29") (pintype "passive"))
    )
    (net (code "165") (name "/SPI1_MISO") (class "Default")
      (node (ref "IC1") (pin "124") (pinfunction "PG9_124") (pintype "passive"))
      (node (ref "IC2") (pin "124") (pinfunction "PG9_124") (pintype "passive"))
    )
    (net (code "166") (name "/SPI1_MOSI") (class "Default")
      (node (ref "IC1") (pin "123") (pinfunction "PD7_123") (pintype "passive"))
      (node (ref "IC2") (pin "123") (pinfunction "PD7_123") (pintype "passive"))
    )
    (net (code "167") (name "/SPI1_NSS") (class "Default")
      (node (ref "IC1") (pin "125") (pinfunction "PG10_125") (pintype "passive"))
      (node (ref "IC2") (pin "125") (pinfunction "PG10_125") (pintype "passive"))
    )
    (net (code "168") (name "/SPI1_SCK") (class "Default")
      (node (ref "IC1") (pin "126") (pinfunction "PG11_126") (pintype "passive"))
      (node (ref "IC2") (pin "126") (pinfunction "PG11_126") (pintype "passive"))
    )
    (net (code "169") (name "/SPI2_MISO") (class "Default")
      (node (ref "IC1") (pin "75") (pinfunction "PB14_75") (pintype "passive"))
      (node (ref "J1") (pin "32") (pinfunction "32_32") (pintype "passive"))
    )
    (net (code "170") (name "/SPI2_MOSI") (class "Default")
      (node (ref "IC1") (pin "76") (pinfunction "PB15_76") (pintype "passive"))
      (node (ref "J1") (pin "34") (pinfunction "34_34") (pintype "passive"))
    )
    (net (code "171") (name "/SPI2_NSS") (class "Default")
      (node (ref "IC1") (pin "73") (pinfunction "PB12_73") (pintype "passive"))
      (node (ref "J1") (pin "28") (pinfunction "28_28") (pintype "passive"))
    )
    (net (code "172") (name "/SPI2_SCK") (class "Default")
      (node (ref "IC1") (pin "74") (pinfunction "PB13_74") (pintype "passive"))
      (node (ref "J1") (pin "30") (pinfunction "30_30") (pintype "passive"))
    )
    (net (code "173") (name "/UART2_RX") (class "Default")
      (node (ref "IC1") (pin "122") (pinfunction "PD6_122") (pintype "passive"))
      (node (ref "IC2") (pin "36") (pinfunction "PA2_36") (pintype "passive"))
    )
    (net (code "174") (name "/UART2_TX") (class "Default")
      (node (ref "IC1") (pin "36") (pinfunction "PA2_36") (pintype "passive"))
      (node (ref "IC2") (pin "37") (pinfunction "PA3_37") (pintype "passive"))
    )
    (net (code "175") (name "/UART4_RX") (class "Default")
      (node (ref "IC1") (pin "35") (pinfunction "PA1_35") (pintype "passive"))
      (node (ref "TP2") (pin "1") (pinfunction "12_1") (pintype "passive"))
    )
    (net (code "176") (name "/UART4_TX") (class "Default")
      (node (ref "IC1") (pin "34") (pinfunction "PA0_34") (pintype "passive"))
      (node (ref "TP1") (pin "1") (pinfunction "12_1") (pintype "passive"))
    )
    (net (code "177") (name "/UDQM") (class "Default")
      (node (ref "IC1") (pin "142") (pinfunction "PE1_142") (pintype "passive"))
      (node (ref "R10") (pin "2") (pinfunction "2_2") (pintype "passive"))
      (node (ref "U1") (pin "39") (pinfunction "UDQM_39") (pintype "passive"))
      (node (ref "U2") (pin "39") (pinfunction "UDQM_39") (pintype "passive"))
    )
    (net (code "178") (name "/UDQM1") (class "Default")
      (node (ref "IC2") (pin "142") (pinfunction "PE1_142") (pintype "passive"))
      (node (ref "R12") (pin "2") (pinfunction "2_2") (pintype "passive"))
      (node (ref "U3") (pin "39") (pinfunction "UDQM_39") (pintype "passive"))
      (node (ref "U4") (pin "39") (pinfunction "UDQM_39") (pintype "passive"))
    )
    (net (code "179") (name "/UI_CLK") (class "Default")
      (node (ref "IC1") (pin "19") (pinfunction "PF7_19") (pintype "passive"))
      (node (ref "R4") (pin "2") (pinfunction "2_2") (pintype "passive"))
    )
    (net (code "180") (name "/UI_CS") (class "Default")
      (node (ref "IC1") (pin "18") (pinfunction "PF6_18") (pintype "passive"))
      (node (ref "R3") (pin "2") (pinfunction "2_2") (pintype "passive"))
    )
    (net (code "181") (name "/UI_MISO") (class "Default")
      (node (ref "IC1") (pin "20") (pinfunction "PF8_20") (pintype "passive"))
      (node (ref "IC4") (pin "4") (pinfunction "Y_4") (pintype "passive"))
    )
    (net (code "182") (name "/UI_MISO_5V") (class "Default")
      (node (ref "IC4") (pin "2") (pinfunction "A_2") (pintype "passive"))
      (node (ref "J3") (pin "34") (pinfunction "34_34") (pintype "passive"))
    )
    (net (code "183") (name "/UI_MOSI") (class "Default")
      (node (ref "IC1") (pin "21") (pinfunction "PF9_21") (pintype "passive"))
      (node (ref "R8") (pin "2") (pinfunction "2_2") (pintype "passive"))
    )
    (net (code "184") (name "/UI_RESET") (class "Default")
      (node (ref "IC1") (pin "7") (pinfunction "PC13_7") (pintype "passive"))
    )
    (net (code "185") (name "/USB_FS_DM") (class "Default")
      (node (ref "IC1") (pin "103") (pinfunction "PA11_103") (pintype "passive"))
      (node (ref "J3") (pin "30") (pinfunction "30_30") (pintype "passive"))
    )
    (net (code "186") (name "/USB_FS_DP") (class "Default")
      (node (ref "IC1") (pin "104") (pinfunction "PA12_104") (pintype "passive"))
      (node (ref "J3") (pin "28") (pinfunction "28_28") (pintype "passive"))
    )
    (net (code "187") (name "/USB_FS_SOF") (class "Default")
      (node (ref "IC1") (pin "100") (pinfunction "PA8_100") (pintype "passive"))
      (node (ref "J1") (pin "40") (pinfunction "40_40") (pintype "passive"))
    )
    (net (code "188") (name "/USB_FS_VBUS") (class "Default")
      (node (ref "IC1") (pin "101") (pinfunction "PA9_101") (pintype "passive"))
      (node (ref "J3") (pin "32") (pinfunction "32_32") (pintype "passive"))
    )
    (net (code "189") (name "GND") (class "Default")
      (node (ref "C1") (pin "2") (pinfunction "2_2") (pintype "passive"))
      (node (ref "C10") (pin "1") (pinfunction "1_1") (pintype "passive"))
      (node (ref "C11") (pin "2") (pinfunction "2_2") (pintype "passive"))
      (node (ref "C12") (pin "2") (pinfunction "2_2") (pintype "passive"))
      (node (ref "C13") (pin "2") (pinfunction "2_2") (pintype "passive"))
      (node (ref "C14") (pin "2") (pinfunction "2_2") (pintype "passive"))
      (node (ref "C15") (pin "2") (pinfunction "2_2") (pintype "passive"))
      (node (ref "C16") (pin "2") (pinfunction "2_2") (pintype "passive"))
      (node (ref "C17") (pin "2") (pinfunction "2_2") (pintype "passive"))
      (node (ref "C18") (pin "2") (pinfunction "2_2") (pintype "passive"))
      (node (ref "C19") (pin "2") (pinfunction "2_2") (pintype "passive"))
      (node (ref "C2") (pin "2") (pinfunction "2_2") (pintype "passive"))
      (node (ref "C20") (pin "2") (pinfunction "2_2") (pintype "passive"))
      (node (ref "C21") (pin "2") (pinfunction "2_2") (pintype "passive"))
      (node (ref "C22") (pin "2") (pinfunction "2_2") (pintype "passive"))
      (node (ref "C23") (pin "2") (pinfunction "2_2") (pintype "passive"))
      (node (ref "C24") (pin "2") (pinfunction "2_2") (pintype "passive"))
      (node (ref "C25") (pin "2") (pinfunction "2_2") (pintype "passive"))
      (node (ref "C26") (pin "2") (pinfunction "2_2") (pintype "passive"))
      (node (ref "C27") (pin "2") (pinfunction "2_2") (pintype "passive"))
      (node (ref "C28") (pin "2") (pinfunction "2_2") (pintype "passive"))
      (node (ref "C29") (pin "2") (pinfunction "2_2") (pintype "passive"))
      (node (ref "C3") (pin "1") (pinfunction "1_1") (pintype "passive"))
      (node (ref "C30") (pin "2") (pinfunction "2_2") (pintype "passive"))
      (node (ref "C31") (pin "2") (pinfunction "2_2") (pintype "passive"))
      (node (ref "C32") (pin "2") (pinfunction "2_2") (pintype "passive"))
      (node (ref "C33") (pin "2") (pinfunction "2_2") (pintype "passive"))
      (node (ref "C34") (pin "2") (pinfunction "2_2") (pintype "passive"))
      (node (ref "C35") (pin "2") (pinfunction "2_2") (pintype "passive"))
      (node (ref "C36") (pin "2") (pinfunction "2_2") (pintype "passive"))
      (node (ref "C37") (pin "2") (pinfunction "2_2") (pintype "passive"))
      (node (ref "C38") (pin "2") (pinfunction "2_2") (pintype "passive"))
      (node (ref "C39") (pin "2") (pinfunction "2_2") (pintype "passive"))
      (node (ref "C4") (pin "1") (pinfunction "1_1") (pintype "passive"))
      (node (ref "C40") (pin "2") (pinfunction "2_2") (pintype "passive"))
      (node (ref "C41") (pin "2") (pinfunction "2_2") (pintype "passive"))
      (node (ref "C42") (pin "2") (pinfunction "2_2") (pintype "passive"))
      (node (ref "C43") (pin "2") (pinfunction "2_2") (pintype "passive"))
      (node (ref "C44") (pin "2") (pinfunction "2_2") (pintype "passive"))
      (node (ref "C45") (pin "2") (pinfunction "2_2") (pintype "passive"))
      (node (ref "C46") (pin "2") (pinfunction "2_2") (pintype "passive"))
      (node (ref "C47") (pin "2") (pinfunction "2_2") (pintype "passive"))
      (node (ref "C48") (pin "2") (pinfunction "2_2") (pintype "passive"))
      (node (ref "C49") (pin "2") (pinfunction "2_2") (pintype "passive"))
      (node (ref "C5") (pin "1") (pinfunction "1_1") (pintype "passive"))
      (node (ref "C50") (pin "2") (pinfunction "2_2") (pintype "passive"))
      (node (ref "C51") (pin "2") (pinfunction "2_2") (pintype "passive"))
      (node (ref "C52") (pin "2") (pinfunction "2_2") (pintype "passive"))
      (node (ref "C53") (pin "2") (pinfunction "2_2") (pintype "passive"))
      (node (ref "C54") (pin "2") (pinfunction "2_2") (pintype "passive"))
      (node (ref "C55") (pin "2") (pinfunction "2_2") (pintype "passive"))
      (node (ref "C56") (pin "2") (pinfunction "2_2") (pintype "passive"))
      (node (ref "C57") (pin "2") (pinfunction "2_2") (pintype "passive"))
      (node (ref "C58") (pin "2") (pinfunction "2_2") (pintype "passive"))
      (node (ref "C59") (pin "2") (pinfunction "2_2") (pintype "passive"))
      (node (ref "C6") (pin "1") (pinfunction "1_1") (pintype "passive"))
      (node (ref "C60") (pin "2") (pinfunction "2_2") (pintype "passive"))
      (node (ref "C61") (pin "1") (pinfunction "1_1") (pintype "passive"))
      (node (ref "C62") (pin "1") (pinfunction "1_1") (pintype "passive"))
      (node (ref "C63") (pin "1") (pinfunction "1_1") (pintype "passive"))
      (node (ref "C64") (pin "1") (pinfunction "1_1") (pintype "passive"))
      (node (ref "C65") (pin "1") (pinfunction "1_1") (pintype "passive"))
      (node (ref "C66") (pin "1") (pinfunction "1_1") (pintype "passive"))
      (node (ref "C67") (pin "1") (pinfunction "1_1") (pintype "passive"))
      (node (ref "C68") (pin "1") (pinfunction "1_1") (pintype "passive"))
      (node (ref "C7") (pin "1") (pinfunction "1_1") (pintype "passive"))
      (node (ref "C8") (pin "1") (pinfunction "1_1") (pintype "passive"))
      (node (ref "C9") (pin "1") (pinfunction "1_1") (pintype "passive"))
      (node (ref "IC1") (pin "107") (pinfunction "VSS_7_107") (pintype "passive"))
      (node (ref "IC1") (pin "120") (pinfunction "VSS_8_120") (pintype "passive"))
      (node (ref "IC1") (pin "130") (pinfunction "VSS_9_130") (pintype "passive"))
      (node (ref "IC1") (pin "16") (pinfunction "VSS_1_16") (pintype "passive"))
      (node (ref "IC1") (pin "31") (pinfunction "VSSA_31") (pintype "passive"))
      (node (ref "IC1") (pin "38") (pinfunction "VSS_2_38") (pintype "passive"))
      (node (ref "IC1") (pin "51") (pinfunction "VSS_3_51") (pintype "passive"))
      (node (ref "IC1") (pin "61") (pinfunction "VSS_4_61") (pintype "passive"))
      (node (ref "IC1") (pin "83") (pinfunction "VSS_5_83") (pintype "passive"))
      (node (ref "IC1") (pin "94") (pinfunction "VSS_6_94") (pintype "passive"))
      (node (ref "IC2") (pin "107") (pinfunction "VSS_7_107") (pintype "passive"))
      (node (ref "IC2") (pin "120") (pinfunction "VSS_8_120") (pintype "passive"))
      (node (ref "IC2") (pin "130") (pinfunction "VSS_9_130") (pintype "passive"))
      (node (ref "IC2") (pin "16") (pinfunction "VSS_1_16") (pintype "passive"))
      (node (ref "IC2") (pin "31") (pinfunction "VSSA_31") (pintype "passive"))
      (node (ref "IC2") (pin "38") (pinfunction "VSS_2_38") (pintype "passive"))
      (node (ref "IC2") (pin "51") (pinfunction "VSS_3_51") (pintype "passive"))
      (node (ref "IC2") (pin "61") (pinfunction "VSS_4_61") (pintype "passive"))
      (node (ref "IC2") (pin "83") (pinfunction "VSS_5_83") (pintype "passive"))
      (node (ref "IC2") (pin "94") (pinfunction "VSS_6_94") (pintype "passive"))
      (node (ref "IC3") (pin "4") (pinfunction "VSS_4") (pintype "passive"))
      (node (ref "IC4") (pin "1") (pinfunction "~{OE}_1") (pintype "passive"))
      (node (ref "IC4") (pin "3") (pinfunction "GND_3") (pintype "passive"))
      (node (ref "IC5") (pin "4") (pinfunction "VSS_4") (pintype "power_in"))
      (node (ref "IC6") (pin "4") (pinfunction "VSS_4") (pintype "power_in"))
      (node (ref "IC7") (pin "7") (pinfunction "WP_7") (pintype "passive"))
      (node (ref "IC8") (pin "7") (pinfunction "WP_7") (pintype "passive"))
      (node (ref "J3") (pin "17") (pinfunction "17_17") (pintype "passive"))
      (node (ref "J3") (pin "19") (pinfunction "19_19") (pintype "passive"))
      (node (ref "J3") (pin "21") (pinfunction "21_21") (pintype "passive"))
      (node (ref "J3") (pin "23") (pinfunction "23_23") (pintype "passive"))
      (node (ref "J3") (pin "25") (pinfunction "25_25") (pintype "passive"))
      (node (ref "J3") (pin "27") (pinfunction "27_27") (pintype "passive"))
      (node (ref "J4") (pin "4") (pinfunction "IN_4") (pintype "passive"))
      (node (ref "J5") (pin "3") (pinfunction "IN_3") (pintype "passive"))
      (node (ref "J6") (pin "3") (pinfunction "IN_3") (pintype "passive"))
      (node (ref "J8") (pin "4") (pinfunction "IN_4") (pintype "passive"))
      (node (ref "R1") (pin "2") (pinfunction "2_2") (pintype "passive"))
      (node (ref "R10") (pin "1") (pinfunction "1_1") (pintype "passive"))
      (node (ref "R12") (pin "1") (pinfunction "1_1") (pintype "passive"))
      (node (ref "R2") (pin "2") (pinfunction "2_2") (pintype "passive"))
      (node (ref "R7") (pin "1") (pinfunction "1_1") (pintype "passive"))
      (node (ref "R9") (pin "1") (pinfunction "1_1") (pintype "passive"))
      (node (ref "U1") (pin "12") (pinfunction "VSSQ_12") (pintype "passive"))
      (node (ref "U1") (pin "28") (pinfunction "VSS_28") (pintype "passive"))
      (node (ref "U1") (pin "41") (pinfunction "VSS_41") (pintype "passive"))
      (node (ref "U1") (pin "46") (pinfunction "VSSQ_46") (pintype "passive"))
      (node (ref "U1") (pin "52") (pinfunction "VSSQ_52") (pintype "passive"))
      (node (ref "U1") (pin "54") (pinfunction "VSS_54") (pintype "passive"))
      (node (ref "U1") (pin "6") (pinfunction "VSSQ_6") (pintype "passive"))
      (node (ref "U2") (pin "12") (pinfunction "VSSQ_12") (pintype "passive"))
      (node (ref "U2") (pin "28") (pinfunction "VSS_28") (pintype "passive"))
      (node (ref "U2") (pin "41") (pinfunction "VSS_41") (pintype "passive"))
      (node (ref "U2") (pin "46") (pinfunction "VSSQ_46") (pintype "passive"))
      (node (ref "U2") (pin "52") (pinfunction "VSSQ_52") (pintype "passive"))
      (node (ref "U2") (pin "54") (pinfunction "VSS_54") (pintype "passive"))
      (node (ref "U2") (pin "6") (pinfunction "VSSQ_6") (pintype "passive"))
      (node (ref "U3") (pin "12") (pinfunction "VSSQ_12") (pintype "passive"))
      (node (ref "U3") (pin "28") (pinfunction "VSS_28") (pintype "passive"))
      (node (ref "U3") (pin "41") (pinfunction "VSS_41") (pintype "passive"))
      (node (ref "U3") (pin "46") (pinfunction "VSSQ_46") (pintype "passive"))
      (node (ref "U3") (pin "52") (pinfunction "VSSQ_52") (pintype "passive"))
      (node (ref "U3") (pin "54") (pinfunction "VSS_54") (pintype "passive"))
      (node (ref "U3") (pin "6") (pinfunction "VSSQ_6") (pintype "passive"))
      (node (ref "U4") (pin "12") (pinfunction "VSSQ_12") (pintype "passive"))
      (node (ref "U4") (pin "28") (pinfunction "VSS_28") (pintype "passive"))
      (node (ref "U4") (pin "41") (pinfunction "VSS_41") (pintype "passive"))
      (node (ref "U4") (pin "46") (pinfunction "VSSQ_46") (pintype "passive"))
      (node (ref "U4") (pin "52") (pinfunction "VSSQ_52") (pintype "passive"))
      (node (ref "U4") (pin "54") (pinfunction "VSS_54") (pintype "passive"))
      (node (ref "U4") (pin "6") (pinfunction "VSSQ_6") (pintype "passive"))
      (node (ref "Y1") (pin "2") (pinfunction "GND_2") (pintype "passive"))
      (node (ref "Y1") (pin "4") (pinfunction "GND_4") (pintype "passive"))
      (node (ref "Y2") (pin "2") (pinfunction "GND_2") (pintype "passive"))
      (node (ref "Y2") (pin "4") (pinfunction "GND_4") (pintype "passive"))
    )
    (net (code "190") (name "Net-(IC1-BOOT0)") (class "Default")
      (node (ref "IC1") (pin "138") (pinfunction "BOOT0_138") (pintype "passive"))
      (node (ref "R1") (pin "1") (pinfunction "1_1") (pintype "passive"))
    )
    (net (code "191") (name "Net-(IC1-PC14-OSC32_IN)") (class "Default")
      (node (ref "C67") (pin "2") (pinfunction "2_2") (pintype "passive"))
      (node (ref "IC1") (pin "8") (pinfunction "PC14-OSC32_IN_8") (pintype "passive"))
      (node (ref "Y3") (pin "2") (pinfunction "2_2") (pintype "passive"))
    )
    (net (code "192") (name "Net-(IC1-PC15-OSC32_OUT)") (class "Default")
      (node (ref "C68") (pin "2") (pinfunction "2_2") (pintype "passive"))
      (node (ref "IC1") (pin "9") (pinfunction "PC15-OSC32_OUT_9") (pintype "passive"))
      (node (ref "Y3") (pin "1") (pinfunction "1_1") (pintype "passive"))
    )
    (net (code "193") (name "Net-(IC1-PH0-OSC_IN)") (class "Default")
      (node (ref "C3") (pin "2") (pinfunction "2_2") (pintype "passive"))
      (node (ref "IC1") (pin "23") (pinfunction "PH0-OSC_IN_23") (pintype "passive"))
      (node (ref "Y1") (pin "1") (pinfunction "1_1") (pintype "passive"))
    )
    (net (code "194") (name "Net-(IC1-PH1-OSC_OUT)") (class "Default")
      (node (ref "C5") (pin "2") (pinfunction "2_2") (pintype "passive"))
      (node (ref "IC1") (pin "24") (pinfunction "PH1-OSC_OUT_24") (pintype "passive"))
      (node (ref "Y1") (pin "3") (pinfunction "3_3") (pintype "passive"))
    )
    (net (code "195") (name "Net-(IC1-VCAP_1)") (class "Default")
      (node (ref "C9") (pin "2") (pinfunction "2_2") (pintype "passive"))
      (node (ref "IC1") (pin "71") (pinfunction "VCAP_1_71") (pintype "passive"))
    )
    (net (code "196") (name "Net-(IC1-VCAP_2)") (class "Default")
      (node (ref "C1") (pin "1") (pinfunction "1_1") (pintype "passive"))
      (node (ref "IC1") (pin "106") (pinfunction "VCAP_2_106") (pintype "passive"))
    )
    (net (code "197") (name "Net-(IC2-BOOT0)") (class "Default")
      (node (ref "IC2") (pin "138") (pinfunction "BOOT0_138") (pintype "passive"))
      (node (ref "R2") (pin "1") (pinfunction "1_1") (pintype "passive"))
    )
    (net (code "198") (name "Net-(IC2-PH0-OSC_IN)") (class "Default")
      (node (ref "C4") (pin "2") (pinfunction "2_2") (pintype "passive"))
      (node (ref "IC2") (pin "23") (pinfunction "PH0-OSC_IN_23") (pintype "passive"))
      (node (ref "Y2") (pin "1") (pinfunction "1_1") (pintype "passive"))
    )
    (net (code "199") (name "Net-(IC2-PH1-OSC_OUT)") (class "Default")
      (node (ref "C6") (pin "2") (pinfunction "2_2") (pintype "passive"))
      (node (ref "IC2") (pin "24") (pinfunction "PH1-OSC_OUT_24") (pintype "passive"))
      (node (ref "Y2") (pin "3") (pinfunction "3_3") (pintype "passive"))
    )
    (net (code "200") (name "Net-(IC2-VCAP_1)") (class "Default")
      (node (ref "C10") (pin "2") (pinfunction "2_2") (pintype "passive"))
      (node (ref "IC2") (pin "71") (pinfunction "VCAP_1_71") (pintype "passive"))
    )
    (net (code "201") (name "Net-(IC2-VCAP_2)") (class "Default")
      (node (ref "C2") (pin "1") (pinfunction "1_1") (pintype "passive"))
      (node (ref "IC2") (pin "106") (pinfunction "VCAP_2_106") (pintype "passive"))
    )
    (net (code "202") (name "Net-(IC3-SIO[2])") (class "Default")
      (node (ref "IC3") (pin "3") (pinfunction "SIO[2]_3") (pintype "passive"))
      (node (ref "IC3") (pin "7") (pinfunction "SIO[3]_7") (pintype "passive"))
      (node (ref "J4") (pin "1") (pinfunction "IN_1") (pintype "passive"))
      (node (ref "J4") (pin "3") (pinfunction "IN_3") (pintype "passive"))
    )
    (net (code "203") (name "Net-(IC7-A0)") (class "Default")
      (node (ref "IC7") (pin "1") (pinfunction "A0_1") (pintype "passive"))
      (node (ref "J5") (pin "2") (pinfunction "IN_2") (pintype "passive"))
      (node (ref "J5") (pin "4") (pinfunction "IN_4") (pintype "passive"))
    )
    (net (code "204") (name "Net-(IC7-A1)") (class "Default")
      (node (ref "IC7") (pin "2") (pinfunction "A1_2") (pintype "passive"))
      (node (ref "IC7") (pin "3") (pinfunction "A2_3") (pintype "passive"))
      (node (ref "IC7") (pin "4") (pinfunction "GND_4") (pintype "passive"))
    )
    (net (code "205") (name "Net-(IC8-A0)") (class "Default")
      (node (ref "IC8") (pin "1") (pinfunction "A0_1") (pintype "passive"))
      (node (ref "J6") (pin "2") (pinfunction "IN_2") (pintype "passive"))
      (node (ref "J6") (pin "4") (pinfunction "IN_4") (pintype "passive"))
    )
    (net (code "206") (name "Net-(J3-Pad36)") (class "Default")
      (node (ref "J3") (pin "36") (pinfunction "36_36") (pintype "passive"))
      (node (ref "R3") (pin "1") (pinfunction "1_1") (pintype "passive"))
    )
    (net (code "207") (name "Net-(J3-Pad38)") (class "Default")
      (node (ref "J3") (pin "38") (pinfunction "38_38") (pintype "passive"))
      (node (ref "R4") (pin "1") (pinfunction "1_1") (pintype "passive"))
    )
    (net (code "208") (name "Net-(J3-Pad40)") (class "Default")
      (node (ref "J3") (pin "40") (pinfunction "40_40") (pintype "passive"))
      (node (ref "R8") (pin "1") (pinfunction "1_1") (pintype "passive"))
    )
    (net (code "209") (name "unconnected-(IC1-PB7-Pad137)") (class "Default")
      (node (ref "IC1") (pin "137") (pinfunction "PB7_137") (pintype "passive"))
    )
    (net (code "210") (name "unconnected-(IC1-PD3-Pad117)") (class "Default")
      (node (ref "IC1") (pin "117") (pinfunction "PD3_117") (pintype "passive"))
    )
    (net (code "211") (name "unconnected-(IC1-PDR_ON-Pad143)") (class "Default")
      (node (ref "IC1") (pin "143") (pinfunction "PDR_ON_143") (pintype "passive"))
    )
    (net (code "212") (name "unconnected-(IC1-PE3-Pad2)") (class "Default")
      (node (ref "IC1") (pin "2") (pinfunction "PE3_2") (pintype "passive"))
    )
    (net (code "213") (name "unconnected-(IC1-PE4-Pad3)") (class "Default")
      (node (ref "IC1") (pin "3") (pinfunction "PE4_3") (pintype "passive"))
    )
    (net (code "214") (name "unconnected-(IC1-PG2-Pad87)") (class "Default")
      (node (ref "IC1") (pin "87") (pinfunction "PG2_87") (pintype "passive"))
    )
    (net (code "215") (name "unconnected-(IC1-PG3-Pad88)") (class "Default")
      (node (ref "IC1") (pin "88") (pinfunction "PG3_88") (pintype "passive"))
    )
    (net (code "216") (name "unconnected-(IC1-PG7-Pad92)") (class "Default")
      (node (ref "IC1") (pin "92") (pinfunction "PG7_92") (pintype "passive"))
    )
    (net (code "217") (name "unconnected-(IC1-PG13-Pad128)") (class "Default")
      (node (ref "IC1") (pin "128") (pinfunction "PG13_128") (pintype "passive"))
    )
    (net (code "218") (name "unconnected-(IC1-PG14-Pad129)") (class "Default")
      (node (ref "IC1") (pin "129") (pinfunction "PG14_129") (pintype "passive"))
    )
    (net (code "219") (name "unconnected-(IC1-VBAT-Pad6)") (class "Default")
      (node (ref "IC1") (pin "6") (pinfunction "VBAT_6") (pintype "passive"))
    )
    (net (code "220") (name "unconnected-(IC1-VDD33USB-Pad95)") (class "Default")
      (node (ref "IC1") (pin "95") (pinfunction "VDD33USB_95") (pintype "passive"))
    )
    (net (code "221") (name "unconnected-(IC2-PA0-Pad34)") (class "Default")
      (node (ref "IC2") (pin "34") (pinfunction "PA0_34") (pintype "passive"))
    )
    (net (code "222") (name "unconnected-(IC2-PA4-Pad40)") (class "Default")
      (node (ref "IC2") (pin "40") (pinfunction "PA4_40") (pintype "passive"))
    )
    (net (code "223") (name "unconnected-(IC2-PA5-Pad41)") (class "Default")
      (node (ref "IC2") (pin "41") (pinfunction "PA5_41") (pintype "passive"))
    )
    (net (code "224") (name "unconnected-(IC2-PA6-Pad42)") (class "Default")
      (node (ref "IC2") (pin "42") (pinfunction "PA6_42") (pintype "passive"))
    )
    (net (code "225") (name "unconnected-(IC2-PA8-Pad100)") (class "Default")
      (node (ref "IC2") (pin "100") (pinfunction "PA8_100") (pintype "passive"))
    )
    (net (code "226") (name "unconnected-(IC2-PA9-Pad101)") (class "Default")
      (node (ref "IC2") (pin "101") (pinfunction "PA9_101") (pintype "passive"))
    )
    (net (code "227") (name "unconnected-(IC2-PA10-Pad102)") (class "Default")
      (node (ref "IC2") (pin "102") (pinfunction "PA10_102") (pintype "passive"))
    )
    (net (code "228") (name "unconnected-(IC2-PA11-Pad103)") (class "Default")
      (node (ref "IC2") (pin "103") (pinfunction "PA11_103") (pintype "passive"))
    )
    (net (code "229") (name "unconnected-(IC2-PA12-Pad104)") (class "Default")
      (node (ref "IC2") (pin "104") (pinfunction "PA12_104") (pintype "passive"))
    )
    (net (code "230") (name "unconnected-(IC2-PB0-Pad46)") (class "Default")
      (node (ref "IC2") (pin "46") (pinfunction "PB0_46") (pintype "passive"))
    )
    (net (code "231") (name "unconnected-(IC2-PB1-Pad47)") (class "Default")
      (node (ref "IC2") (pin "47") (pinfunction "PB1_47") (pintype "passive"))
    )
    (net (code "232") (name "unconnected-(IC2-PB2-Pad48)") (class "Default")
      (node (ref "IC2") (pin "48") (pinfunction "PB2_48") (pintype "passive"))
    )
    (net (code "233") (name "unconnected-(IC2-PB7-Pad137)") (class "Default")
      (node (ref "IC2") (pin "137") (pinfunction "PB7_137") (pintype "passive"))
    )
    (net (code "234") (name "unconnected-(IC2-PB8-Pad139)") (class "Default")
      (node (ref "IC2") (pin "139") (pinfunction "PB8_139") (pintype "passive"))
    )
    (net (code "235") (name "unconnected-(IC2-PB9-Pad140)") (class "Default")
      (node (ref "IC2") (pin "140") (pinfunction "PB9_140") (pintype "passive"))
    )
    (net (code "236") (name "unconnected-(IC2-PB10-Pad69)") (class "Default")
      (node (ref "IC2") (pin "69") (pinfunction "PB10_69") (pintype "passive"))
    )
    (net (code "237") (name "unconnected-(IC2-PB11-Pad70)") (class "Default")
      (node (ref "IC2") (pin "70") (pinfunction "PB11_70") (pintype "passive"))
    )
    (net (code "238") (name "unconnected-(IC2-PC0-Pad26)") (class "Default")
      (node (ref "IC2") (pin "26") (pinfunction "PC0_26") (pintype "passive"))
    )
    (net (code "239") (name "unconnected-(IC2-PC2_C-Pad28)") (class "Default")
      (node (ref "IC2") (pin "28") (pinfunction "PC2_C_28") (pintype "passive"))
    )
    (net (code "240") (name "unconnected-(IC2-PC5-Pad45)") (class "Default")
      (node (ref "IC2") (pin "45") (pinfunction "PC5_45") (pintype "passive"))
    )
    (net (code "241") (name "unconnected-(IC2-PC6-Pad96)") (class "Default")
      (node (ref "IC2") (pin "96") (pinfunction "PC6_96") (pintype "passive"))
    )
    (net (code "242") (name "unconnected-(IC2-PC7-Pad97)") (class "Default")
      (node (ref "IC2") (pin "97") (pinfunction "PC7_97") (pintype "passive"))
    )
    (net (code "243") (name "unconnected-(IC2-PC8-Pad98)") (class "Default")
      (node (ref "IC2") (pin "98") (pinfunction "PC8_98") (pintype "passive"))
    )
    (net (code "244") (name "unconnected-(IC2-PC9-Pad99)") (class "Default")
      (node (ref "IC2") (pin "99") (pinfunction "PC9_99") (pintype "passive"))
    )
    (net (code "245") (name "unconnected-(IC2-PC10-Pad111)") (class "Default")
      (node (ref "IC2") (pin "111") (pinfunction "PC10_111") (pintype "passive"))
    )
    (net (code "246") (name "unconnected-(IC2-PC11-Pad112)") (class "Default")
      (node (ref "IC2") (pin "112") (pinfunction "PC11_112") (pintype "passive"))
    )
    (net (code "247") (name "unconnected-(IC2-PC12-Pad113)") (class "Default")
      (node (ref "IC2") (pin "113") (pinfunction "PC12_113") (pintype "passive"))
    )
    (net (code "248") (name "unconnected-(IC2-PC14-OSC32_IN-Pad8)") (class "Default")
      (node (ref "IC2") (pin "8") (pinfunction "PC14-OSC32_IN_8") (pintype "passive"))
    )
    (net (code "249") (name "unconnected-(IC2-PC15-OSC32_OUT-Pad9)") (class "Default")
      (node (ref "IC2") (pin "9") (pinfunction "PC15-OSC32_OUT_9") (pintype "passive"))
    )
    (net (code "250") (name "unconnected-(IC2-PD2-Pad116)") (class "Default")
      (node (ref "IC2") (pin "116") (pinfunction "PD2_116") (pintype "passive"))
    )
    (net (code "251") (name "unconnected-(IC2-PD3-Pad117)") (class "Default")
      (node (ref "IC2") (pin "117") (pinfunction "PD3_117") (pintype "passive"))
    )
    (net (code "252") (name "unconnected-(IC2-PD4-Pad118)") (class "Default")
      (node (ref "IC2") (pin "118") (pinfunction "PD4_118") (pintype "passive"))
    )
    (net (code "253") (name "unconnected-(IC2-PD5-Pad119)") (class "Default")
      (node (ref "IC2") (pin "119") (pinfunction "PD5_119") (pintype "passive"))
    )
    (net (code "254") (name "unconnected-(IC2-PD6-Pad122)") (class "Default")
      (node (ref "IC2") (pin "122") (pinfunction "PD6_122") (pintype "passive"))
    )
    (net (code "255") (name "unconnected-(IC2-PD11-Pad80)") (class "Default")
      (node (ref "IC2") (pin "80") (pinfunction "PD11_80") (pintype "passive"))
    )
    (net (code "256") (name "unconnected-(IC2-PDR_ON-Pad143)") (class "Default")
      (node (ref "IC2") (pin "143") (pinfunction "PDR_ON_143") (pintype "passive"))
    )
    (net (code "257") (name "unconnected-(IC2-PG2-Pad87)") (class "Default")
      (node (ref "IC2") (pin "87") (pinfunction "PG2_87") (pintype "passive"))
    )
    (net (code "258") (name "unconnected-(IC2-PG3-Pad88)") (class "Default")
      (node (ref "IC2") (pin "88") (pinfunction "PG3_88") (pintype "passive"))
    )
    (net (code "259") (name "unconnected-(IC2-PG7-Pad92)") (class "Default")
      (node (ref "IC2") (pin "92") (pinfunction "PG7_92") (pintype "passive"))
    )
    (net (code "260") (name "unconnected-(IC2-PG12-Pad127)") (class "Default")
      (node (ref "IC2") (pin "127") (pinfunction "PG12_127") (pintype "passive"))
    )
    (net (code "261") (name "unconnected-(IC2-PG13-Pad128)") (class "Default")
      (node (ref "IC2") (pin "128") (pinfunction "PG13_128") (pintype "passive"))
    )
    (net (code "262") (name "unconnected-(IC2-PG14-Pad129)") (class "Default")
      (node (ref "IC2") (pin "129") (pinfunction "PG14_129") (pintype "passive"))
    )
    (net (code "263") (name "unconnected-(IC2-VBAT-Pad6)") (class "Default")
      (node (ref "IC2") (pin "6") (pinfunction "VBAT_6") (pintype "passive"))
    )
    (net (code "264") (name "unconnected-(IC2-VDD33USB-Pad95)") (class "Default")
      (node (ref "IC2") (pin "95") (pinfunction "VDD33USB_95") (pintype "passive"))
    )
    (net (code "265") (name "unconnected-(IC8-A1-Pad2)") (class "Default")
      (node (ref "IC8") (pin "2") (pinfunction "A1_2") (pintype "passive"))
    )
    (net (code "266") (name "unconnected-(IC8-A2-Pad3)") (class "Default")
      (node (ref "IC8") (pin "3") (pinfunction "A2_3") (pintype "passive"))
    )
    (net (code "267") (name "unconnected-(IC8-GND-Pad4)") (class "Default")
      (node (ref "IC8") (pin "4") (pinfunction "GND_4") (pintype "passive"))
    )
    (net (code "268") (name "unconnected-(J2-Pad1)") (class "Default")
      (node (ref "J2") (pin "1") (pinfunction "1_1") (pintype "passive"))
    )
    (net (code "269") (name "unconnected-(J2-Pad2)") (class "Default")
      (node (ref "J2") (pin "2") (pinfunction "2_2") (pintype "passive+no_connect"))
    )
    (net (code "270") (name "unconnected-(J2-Pad3)") (class "Default")
      (node (ref "J2") (pin "3") (pinfunction "3_3") (pintype "passive"))
    )
    (net (code "271") (name "unconnected-(J2-Pad4)") (class "Default")
      (node (ref "J2") (pin "4") (pinfunction "4_4") (pintype "passive+no_connect"))
    )
    (net (code "272") (name "unconnected-(J2-Pad5)") (class "Default")
      (node (ref "J2") (pin "5") (pinfunction "5_5") (pintype "passive"))
    )
    (net (code "273") (name "unconnected-(J2-Pad6)") (class "Default")
      (node (ref "J2") (pin "6") (pinfunction "6_6") (pintype "passive+no_connect"))
    )
    (net (code "274") (name "unconnected-(J2-Pad7)") (class "Default")
      (node (ref "J2") (pin "7") (pinfunction "7_7") (pintype "passive"))
    )
    (net (code "275") (name "unconnected-(J2-Pad8)") (class "Default")
      (node (ref "J2") (pin "8") (pinfunction "8_8") (pintype "passive+no_connect"))
    )
    (net (code "276") (name "unconnected-(J2-Pad9)") (class "Default")
      (node (ref "J2") (pin "9") (pinfunction "9_9") (pintype "passive"))
    )
    (net (code "277") (name "unconnected-(J2-Pad10)") (class "Default")
      (node (ref "J2") (pin "10") (pinfunction "10_10") (pintype "passive"))
    )
    (net (code "278") (name "unconnected-(J2-Pad11)") (class "Default")
      (node (ref "J2") (pin "11") (pinfunction "11_11") (pintype "passive"))
    )
    (net (code "279") (name "unconnected-(J2-Pad12)") (class "Default")
      (node (ref "J2") (pin "12") (pinfunction "12_12") (pintype "passive"))
    )
    (net (code "280") (name "unconnected-(J2-Pad13)") (class "Default")
      (node (ref "J2") (pin "13") (pinfunction "13_13") (pintype "passive"))
    )
    (net (code "281") (name "unconnected-(J2-Pad14)") (class "Default")
      (node (ref "J2") (pin "14") (pinfunction "14_14") (pintype "passive"))
    )
    (net (code "282") (name "unconnected-(J2-Pad15)") (class "Default")
      (node (ref "J2") (pin "15") (pinfunction "15_15") (pintype "passive"))
    )
    (net (code "283") (name "unconnected-(J2-Pad16)") (class "Default")
      (node (ref "J2") (pin "16") (pinfunction "16_16") (pintype "passive"))
    )
    (net (code "284") (name "unconnected-(J2-Pad17)") (class "Default")
      (node (ref "J2") (pin "17") (pinfunction "17_17") (pintype "passive"))
    )
    (net (code "285") (name "unconnected-(J2-Pad18)") (class "Default")
      (node (ref "J2") (pin "18") (pinfunction "18_18") (pintype "passive"))
    )
    (net (code "286") (name "unconnected-(J2-Pad19)") (class "Default")
      (node (ref "J2") (pin "19") (pinfunction "19_19") (pintype "passive"))
    )
    (net (code "287") (name "unconnected-(J2-Pad20)") (class "Default")
      (node (ref "J2") (pin "20") (pinfunction "20_20") (pintype "passive"))
    )
    (net (code "288") (name "unconnected-(J2-Pad21)") (class "Default")
      (node (ref "J2") (pin "21") (pinfunction "21_21") (pintype "passive"))
    )
    (net (code "289") (name "unconnected-(J2-Pad22)") (class "Default")
      (node (ref "J2") (pin "22") (pinfunction "22_22") (pintype "passive"))
    )
    (net (code "290") (name "unconnected-(J2-Pad23)") (class "Default")
      (node (ref "J2") (pin "23") (pinfunction "23_23") (pintype "passive"))
    )
    (net (code "291") (name "unconnected-(J2-Pad24)") (class "Default")
      (node (ref "J2") (pin "24") (pinfunction "24_24") (pintype "passive"))
    )
    (net (code "292") (name "unconnected-(J2-Pad25)") (class "Default")
      (node (ref "J2") (pin "25") (pinfunction "25_25") (pintype "passive"))
    )
    (net (code "293") (name "unconnected-(J2-Pad26)") (class "Default")
      (node (ref "J2") (pin "26") (pinfunction "26_26") (pintype "passive"))
    )
    (net (code "294") (name "unconnected-(J2-Pad27)") (class "Default")
      (node (ref "J2") (pin "27") (pinfunction "27_27") (pintype "passive"))
    )
    (net (code "295") (name "unconnected-(J2-Pad28)") (class "Default")
      (node (ref "J2") (pin "28") (pinfunction "28_28") (pintype "passive"))
    )
    (net (code "296") (name "unconnected-(J2-Pad29)") (class "Default")
      (node (ref "J2") (pin "29") (pinfunction "29_29") (pintype "passive"))
    )
    (net (code "297") (name "unconnected-(J2-Pad30)") (class "Default")
      (node (ref "J2") (pin "30") (pinfunction "30_30") (pintype "passive"))
    )
    (net (code "298") (name "unconnected-(J2-Pad31)") (class "Default")
      (node (ref "J2") (pin "31") (pinfunction "31_31") (pintype "passive"))
    )
    (net (code "299") (name "unconnected-(J2-Pad32)") (class "Default")
      (node (ref "J2") (pin "32") (pinfunction "32_32") (pintype "passive"))
    )
    (net (code "300") (name "unconnected-(J2-Pad33)") (class "Default")
      (node (ref "J2") (pin "33") (pinfunction "33_33") (pintype "passive"))
    )
    (net (code "301") (name "unconnected-(J2-Pad34)") (class "Default")
      (node (ref "J2") (pin "34") (pinfunction "34_34") (pintype "passive"))
    )
    (net (code "302") (name "unconnected-(J2-Pad35)") (class "Default")
      (node (ref "J2") (pin "35") (pinfunction "35_35") (pintype "passive"))
    )
    (net (code "303") (name "unconnected-(J2-Pad36)") (class "Default")
      (node (ref "J2") (pin "36") (pinfunction "36_36") (pintype "passive"))
    )
    (net (code "304") (name "unconnected-(J2-Pad37)") (class "Default")
      (node (ref "J2") (pin "37") (pinfunction "37_37") (pintype "passive"))
    )
    (net (code "305") (name "unconnected-(J2-Pad38)") (class "Default")
      (node (ref "J2") (pin "38") (pinfunction "38_38") (pintype "passive"))
    )
    (net (code "306") (name "unconnected-(J2-Pad39)") (class "Default")
      (node (ref "J2") (pin "39") (pinfunction "39_39") (pintype "passive"))
    )
    (net (code "307") (name "unconnected-(J2-Pad40)") (class "Default")
      (node (ref "J2") (pin "40") (pinfunction "40_40") (pintype "passive"))
    )
    (net (code "308") (name "unconnected-(J2-Pad41)") (class "Default")
      (node (ref "J2") (pin "41") (pinfunction "41_41") (pintype "passive"))
    )
    (net (code "309") (name "unconnected-(U1-NC-Pad36)") (class "Default")
      (node (ref "U1") (pin "36") (pinfunction "NC_36") (pintype "passive"))
    )
    (net (code "310") (name "unconnected-(U1-NC-Pad40)") (class "Default")
      (node (ref "U1") (pin "40") (pinfunction "NC_40") (pintype "passive"))
    )
    (net (code "311") (name "unconnected-(U2-NC-Pad36)") (class "Default")
      (node (ref "U2") (pin "36") (pinfunction "NC_36") (pintype "passive"))
    )
    (net (code "312") (name "unconnected-(U2-NC-Pad40)") (class "Default")
      (node (ref "U2") (pin "40") (pinfunction "NC_40") (pintype "passive"))
    )
    (net (code "313") (name "unconnected-(U3-NC-Pad36)") (class "Default")
      (node (ref "U3") (pin "36") (pinfunction "NC_36") (pintype "passive"))
    )
    (net (code "314") (name "unconnected-(U3-NC-Pad40)") (class "Default")
      (node (ref "U3") (pin "40") (pinfunction "NC_40") (pintype "passive"))
    )
    (net (code "315") (name "unconnected-(U4-NC-Pad36)") (class "Default")
      (node (ref "U4") (pin "36") (pinfunction "NC_36") (pintype "passive"))
    )
    (net (code "316") (name "unconnected-(U4-NC-Pad40)") (class "Default")
      (node (ref "U4") (pin "40") (pinfunction "NC_40") (pintype "passive"))
    )
  )
)
